# ActuatorBoard.net
KiCad netlist of a schematic drawn in EAGLE
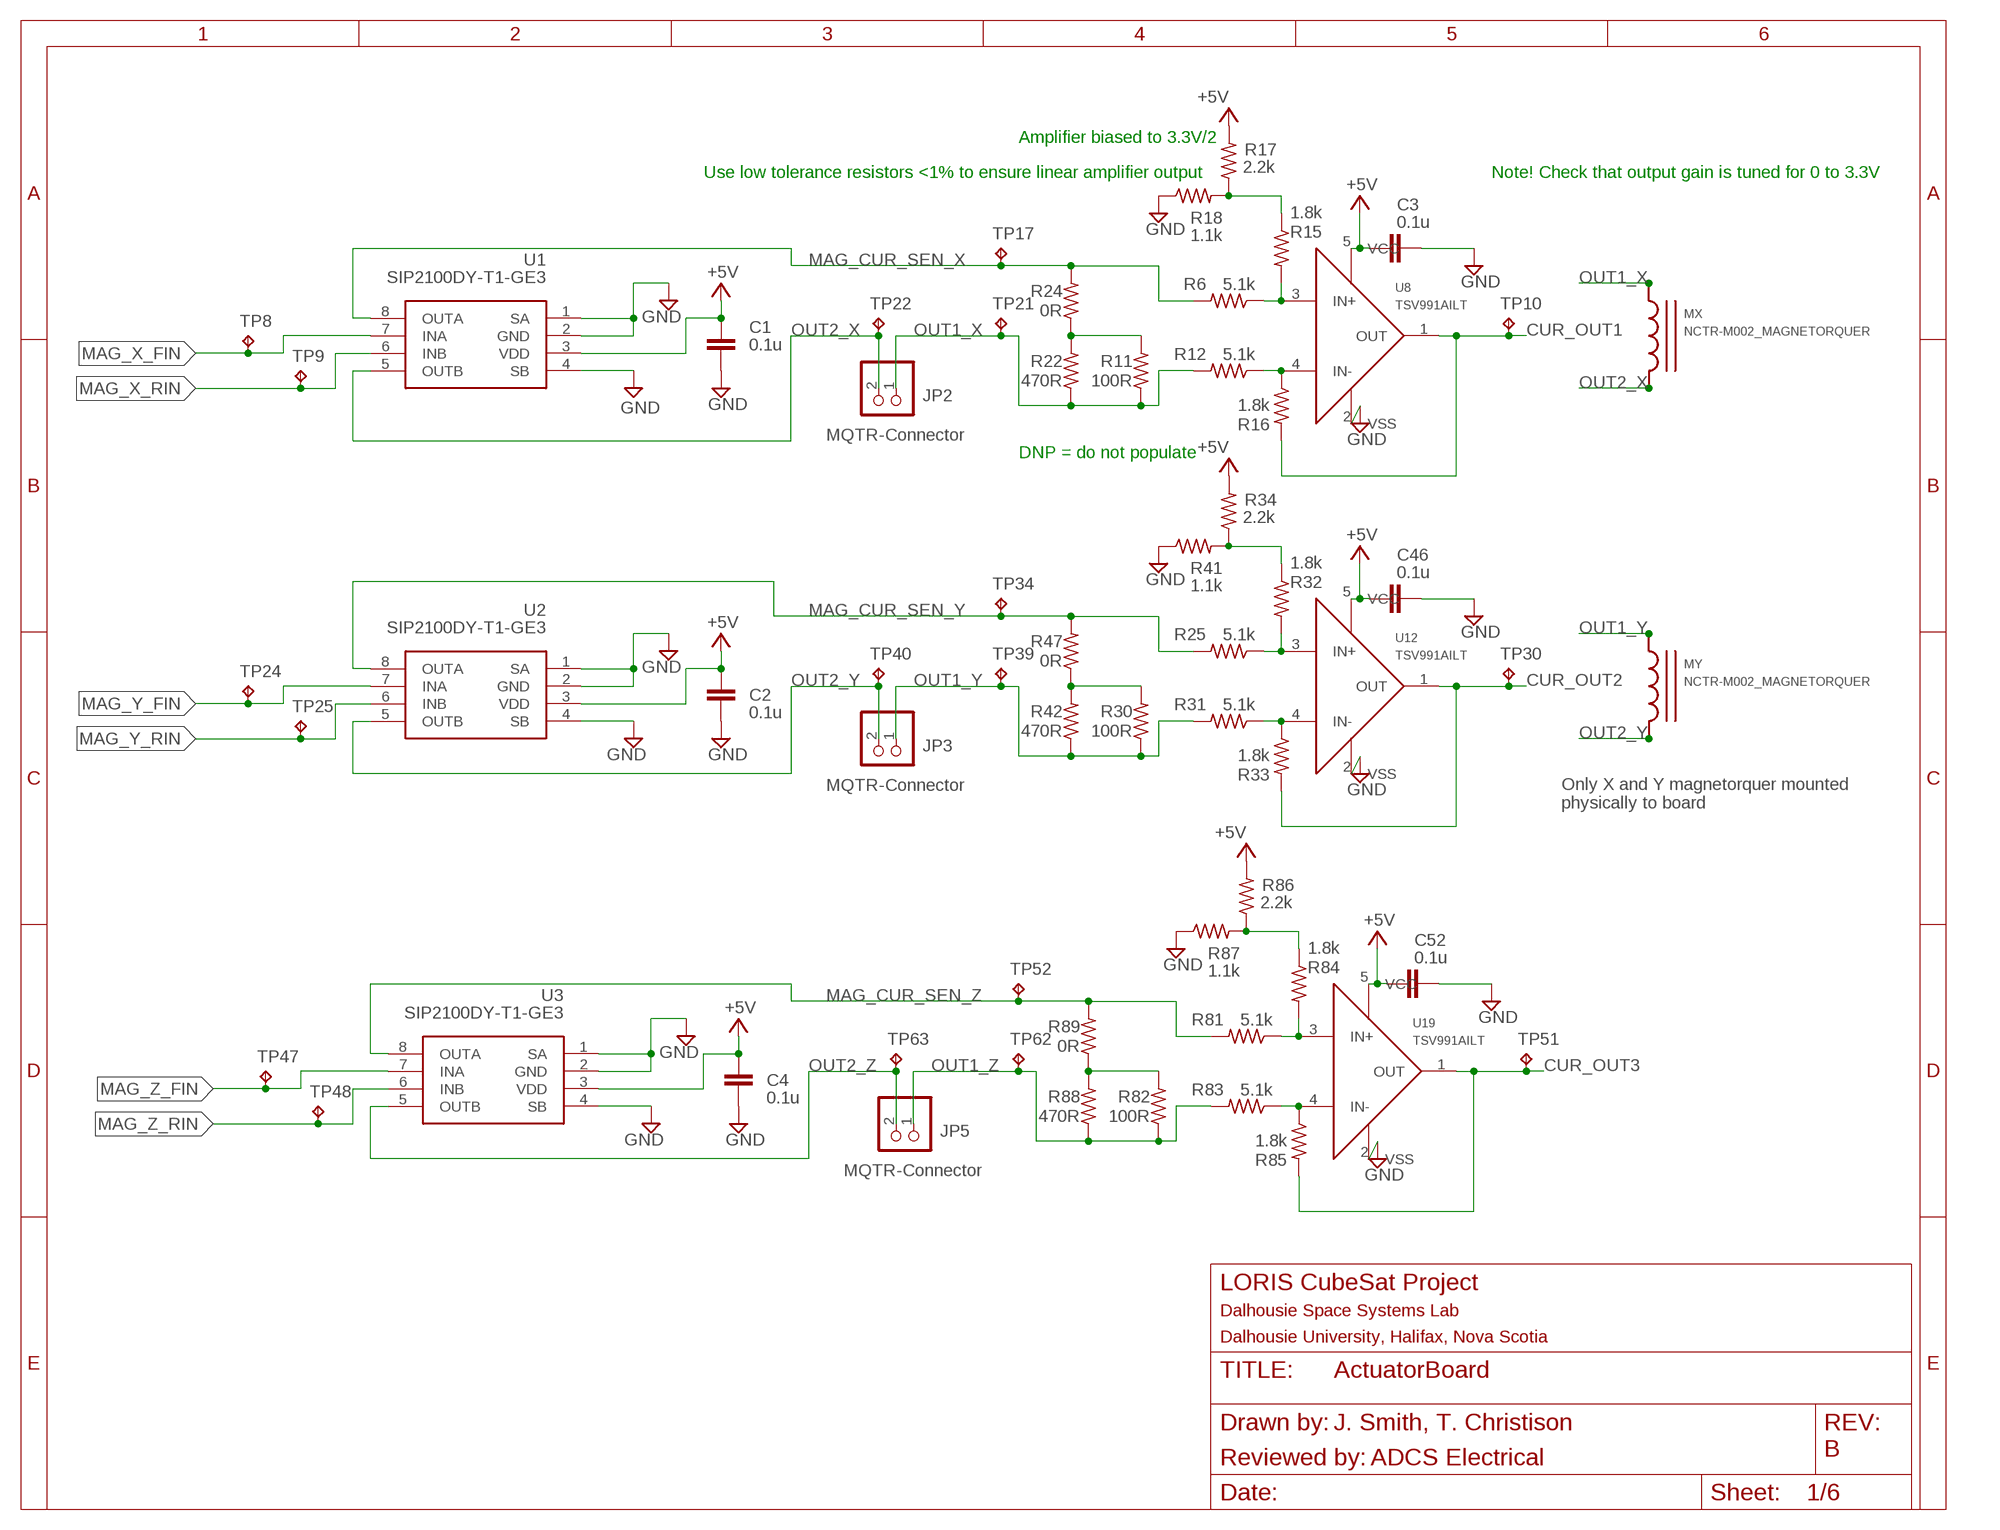
[diagram p0: schematic, sheet 1]
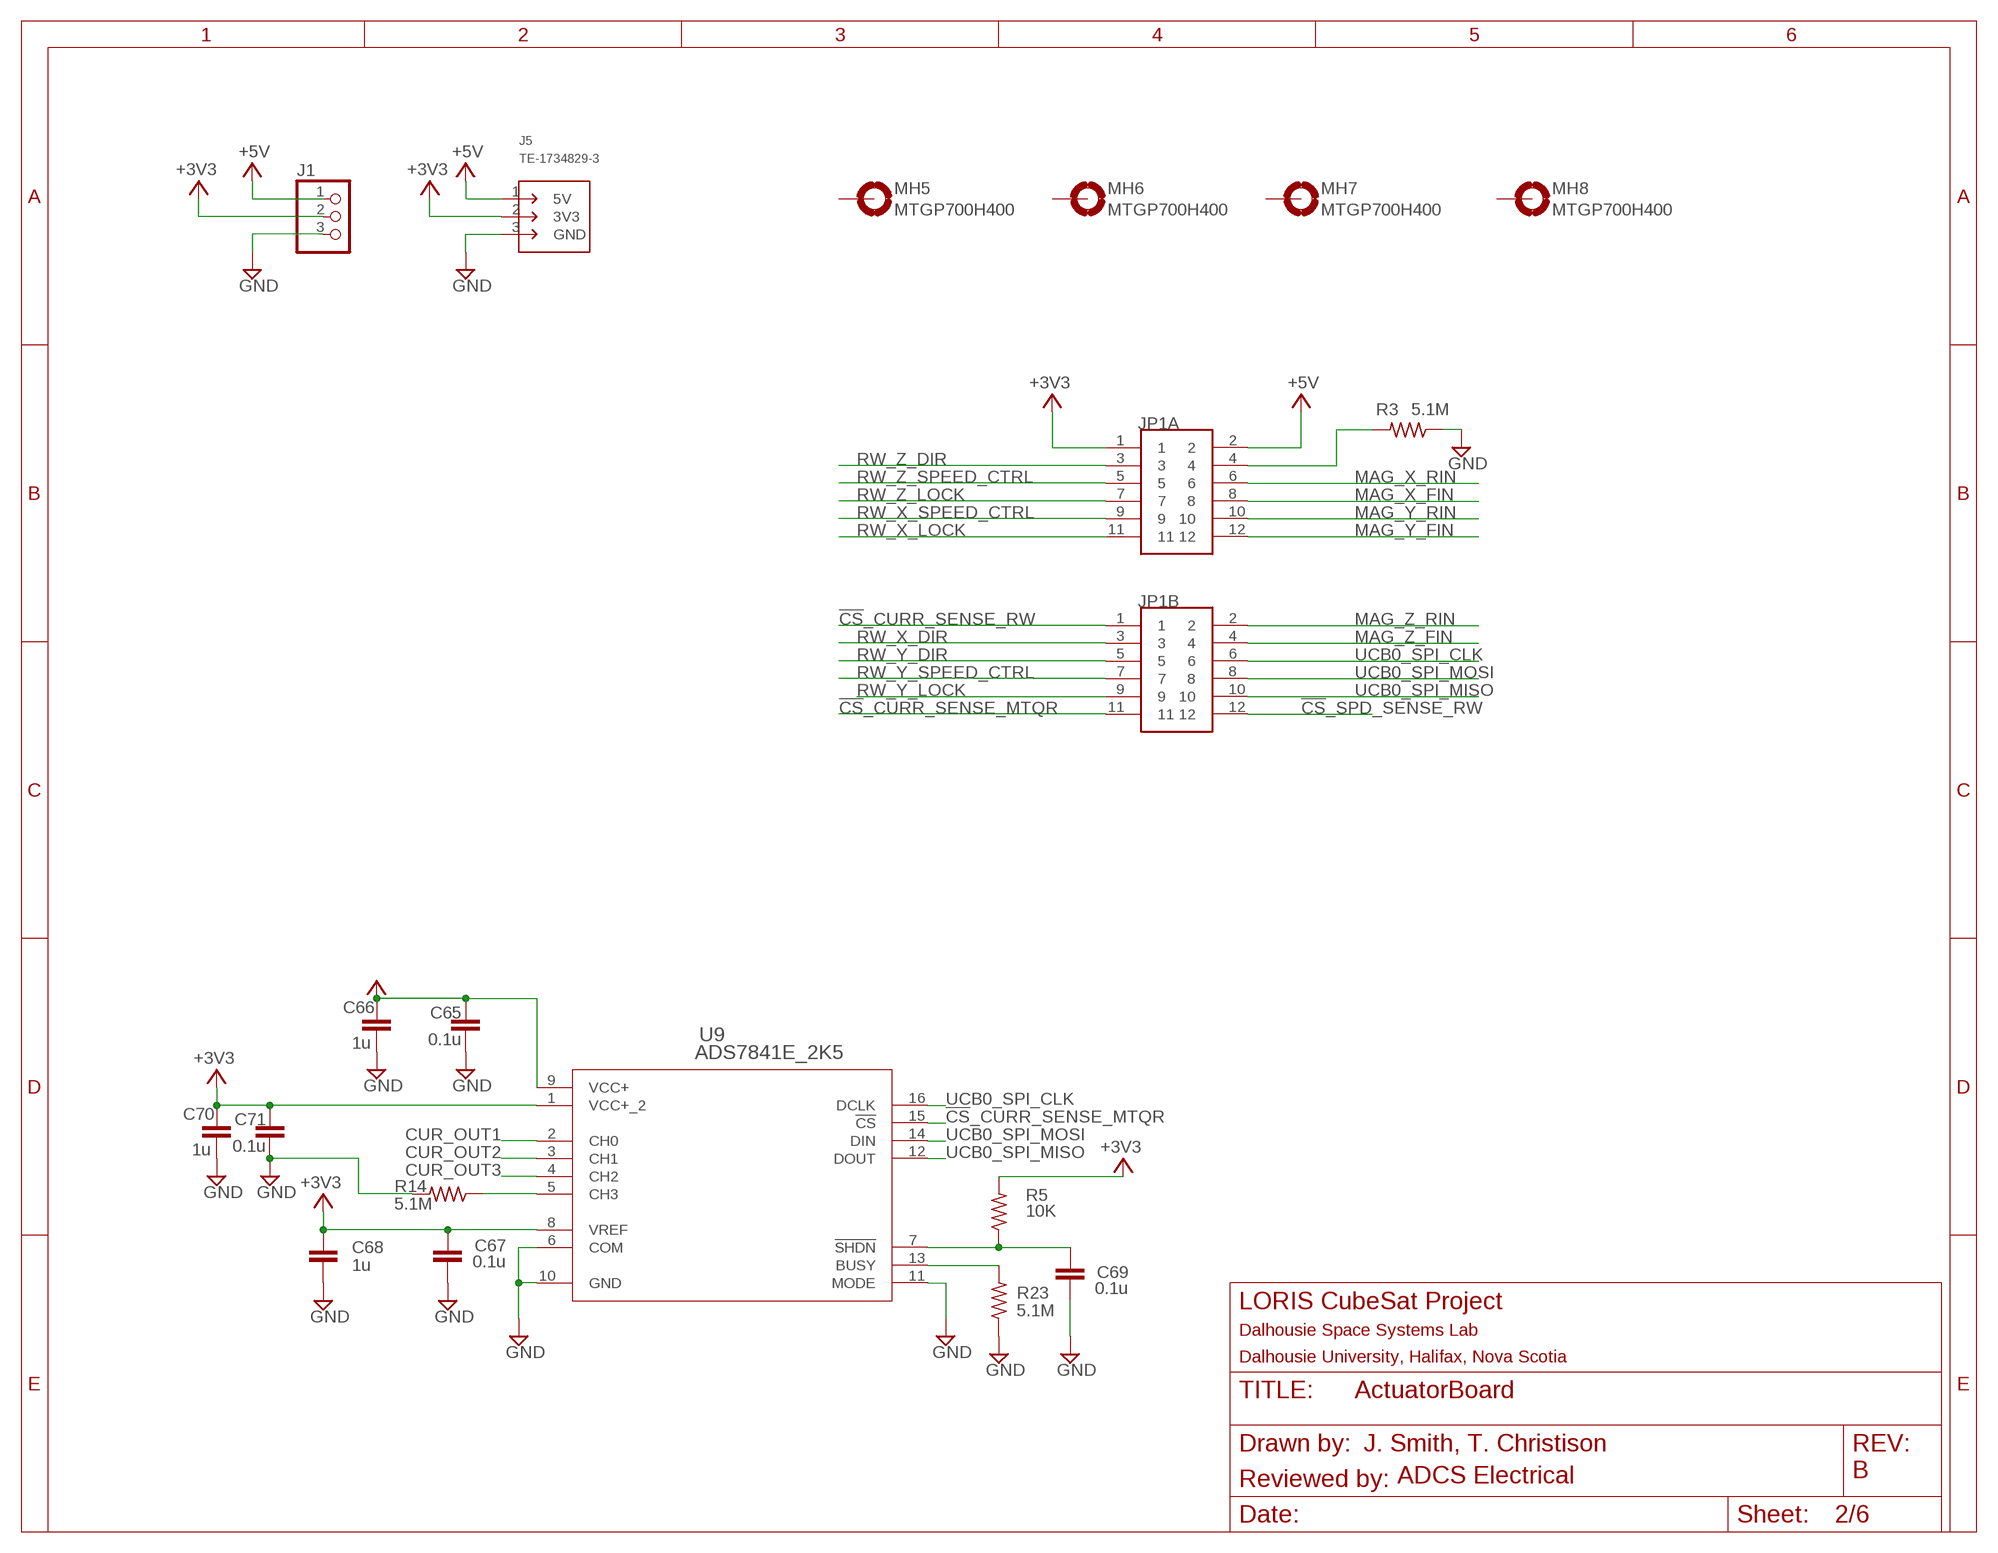
[diagram p1: schematic, sheet 2]
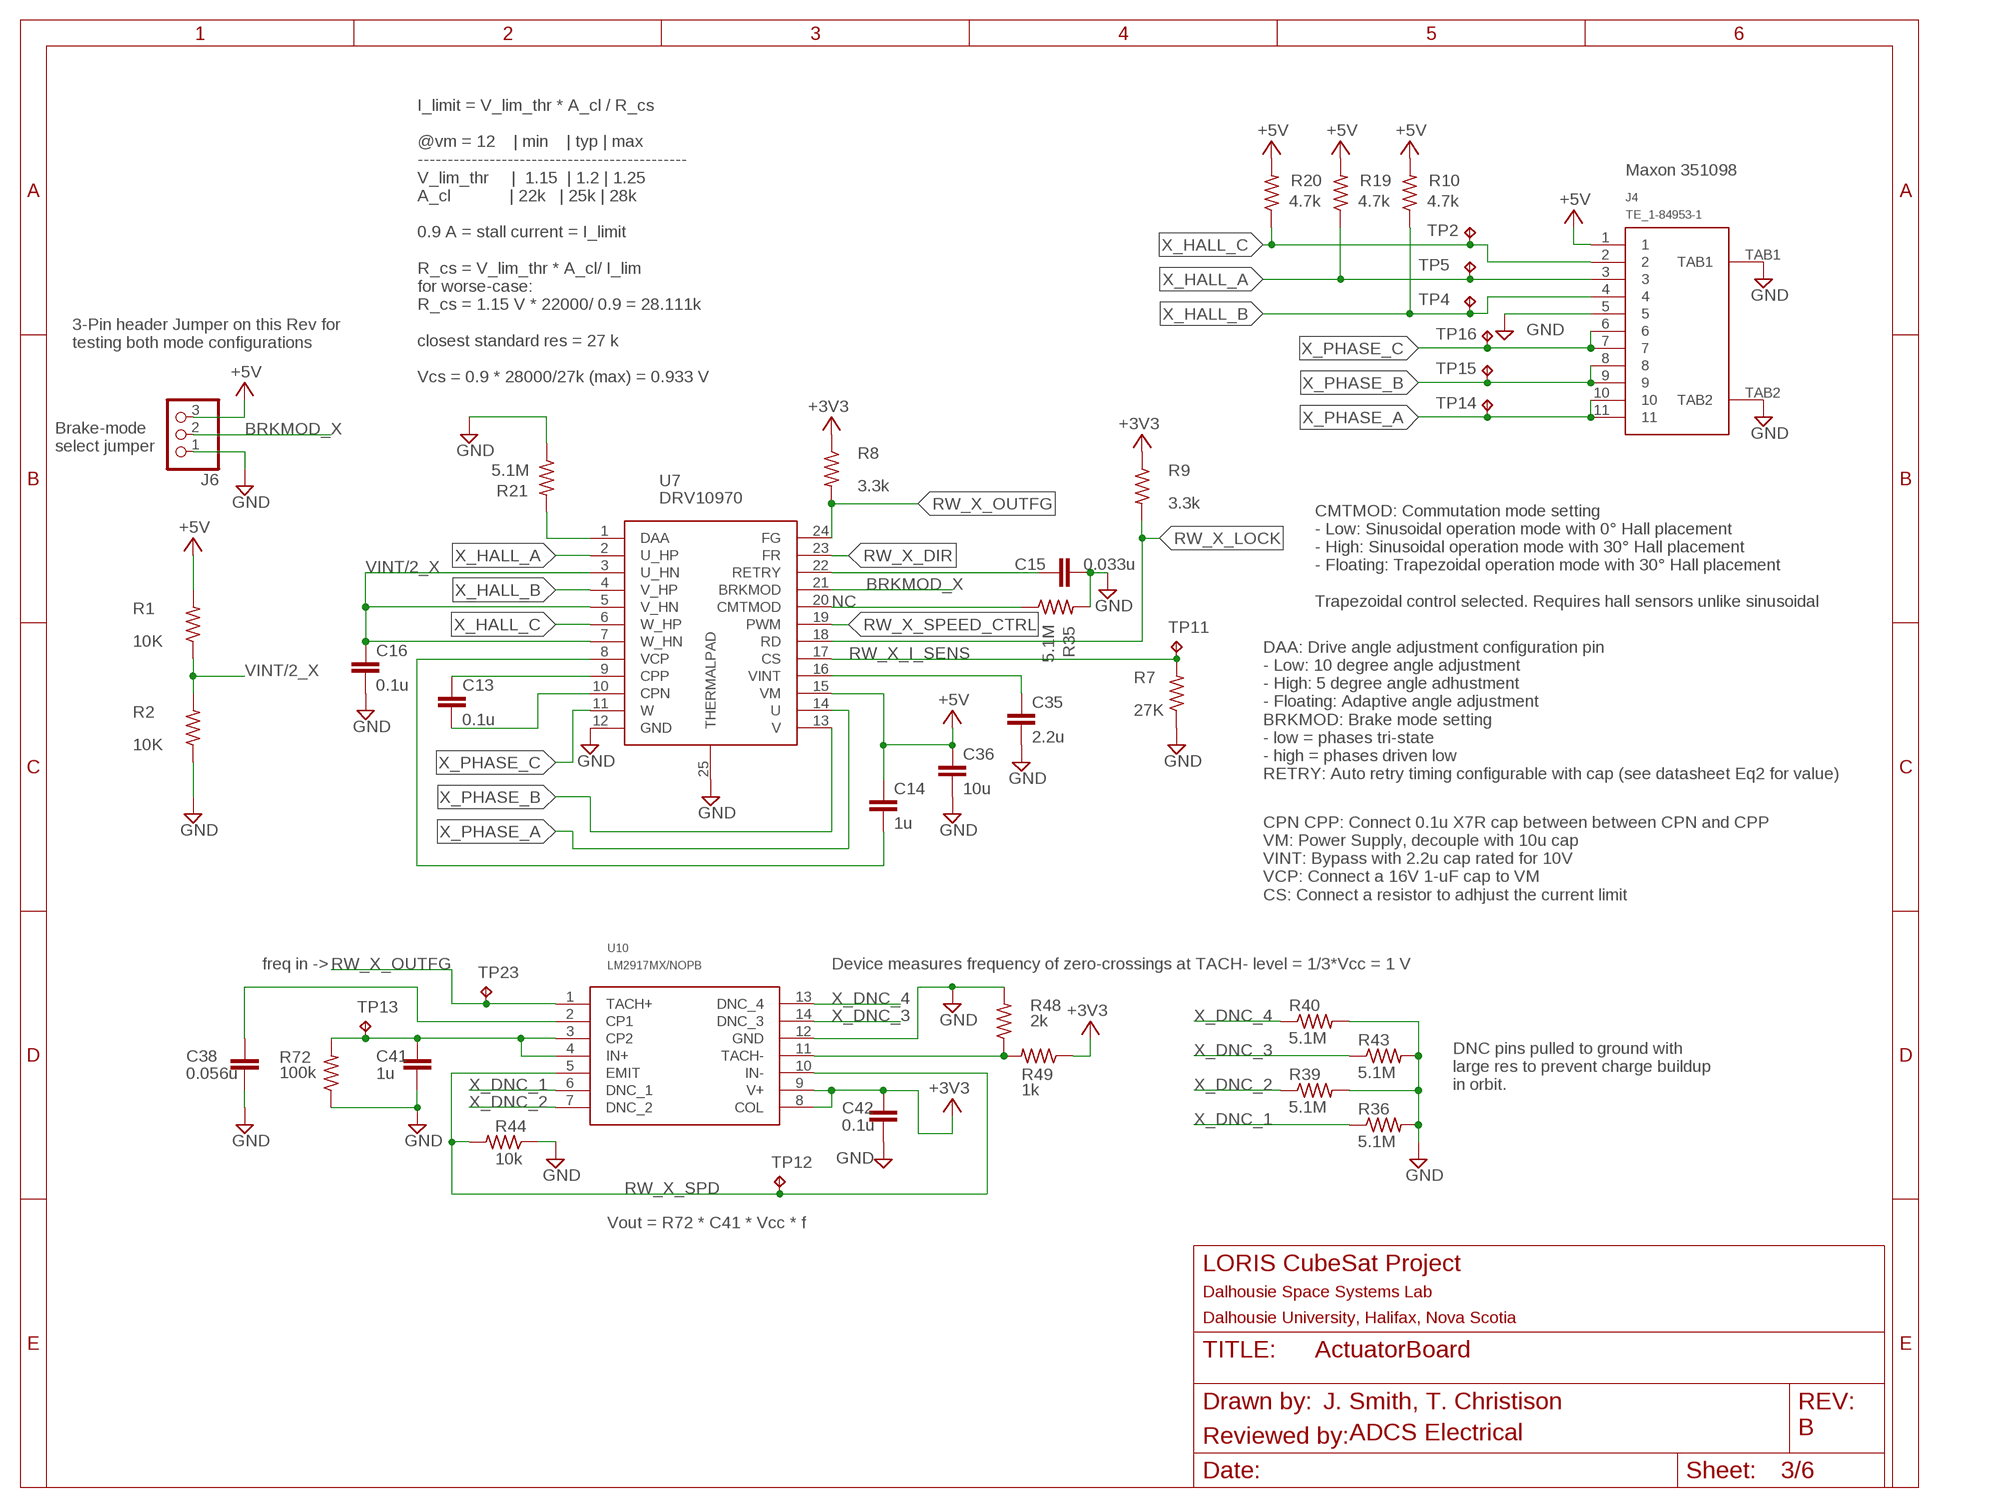
[diagram p2: schematic, sheet 3]
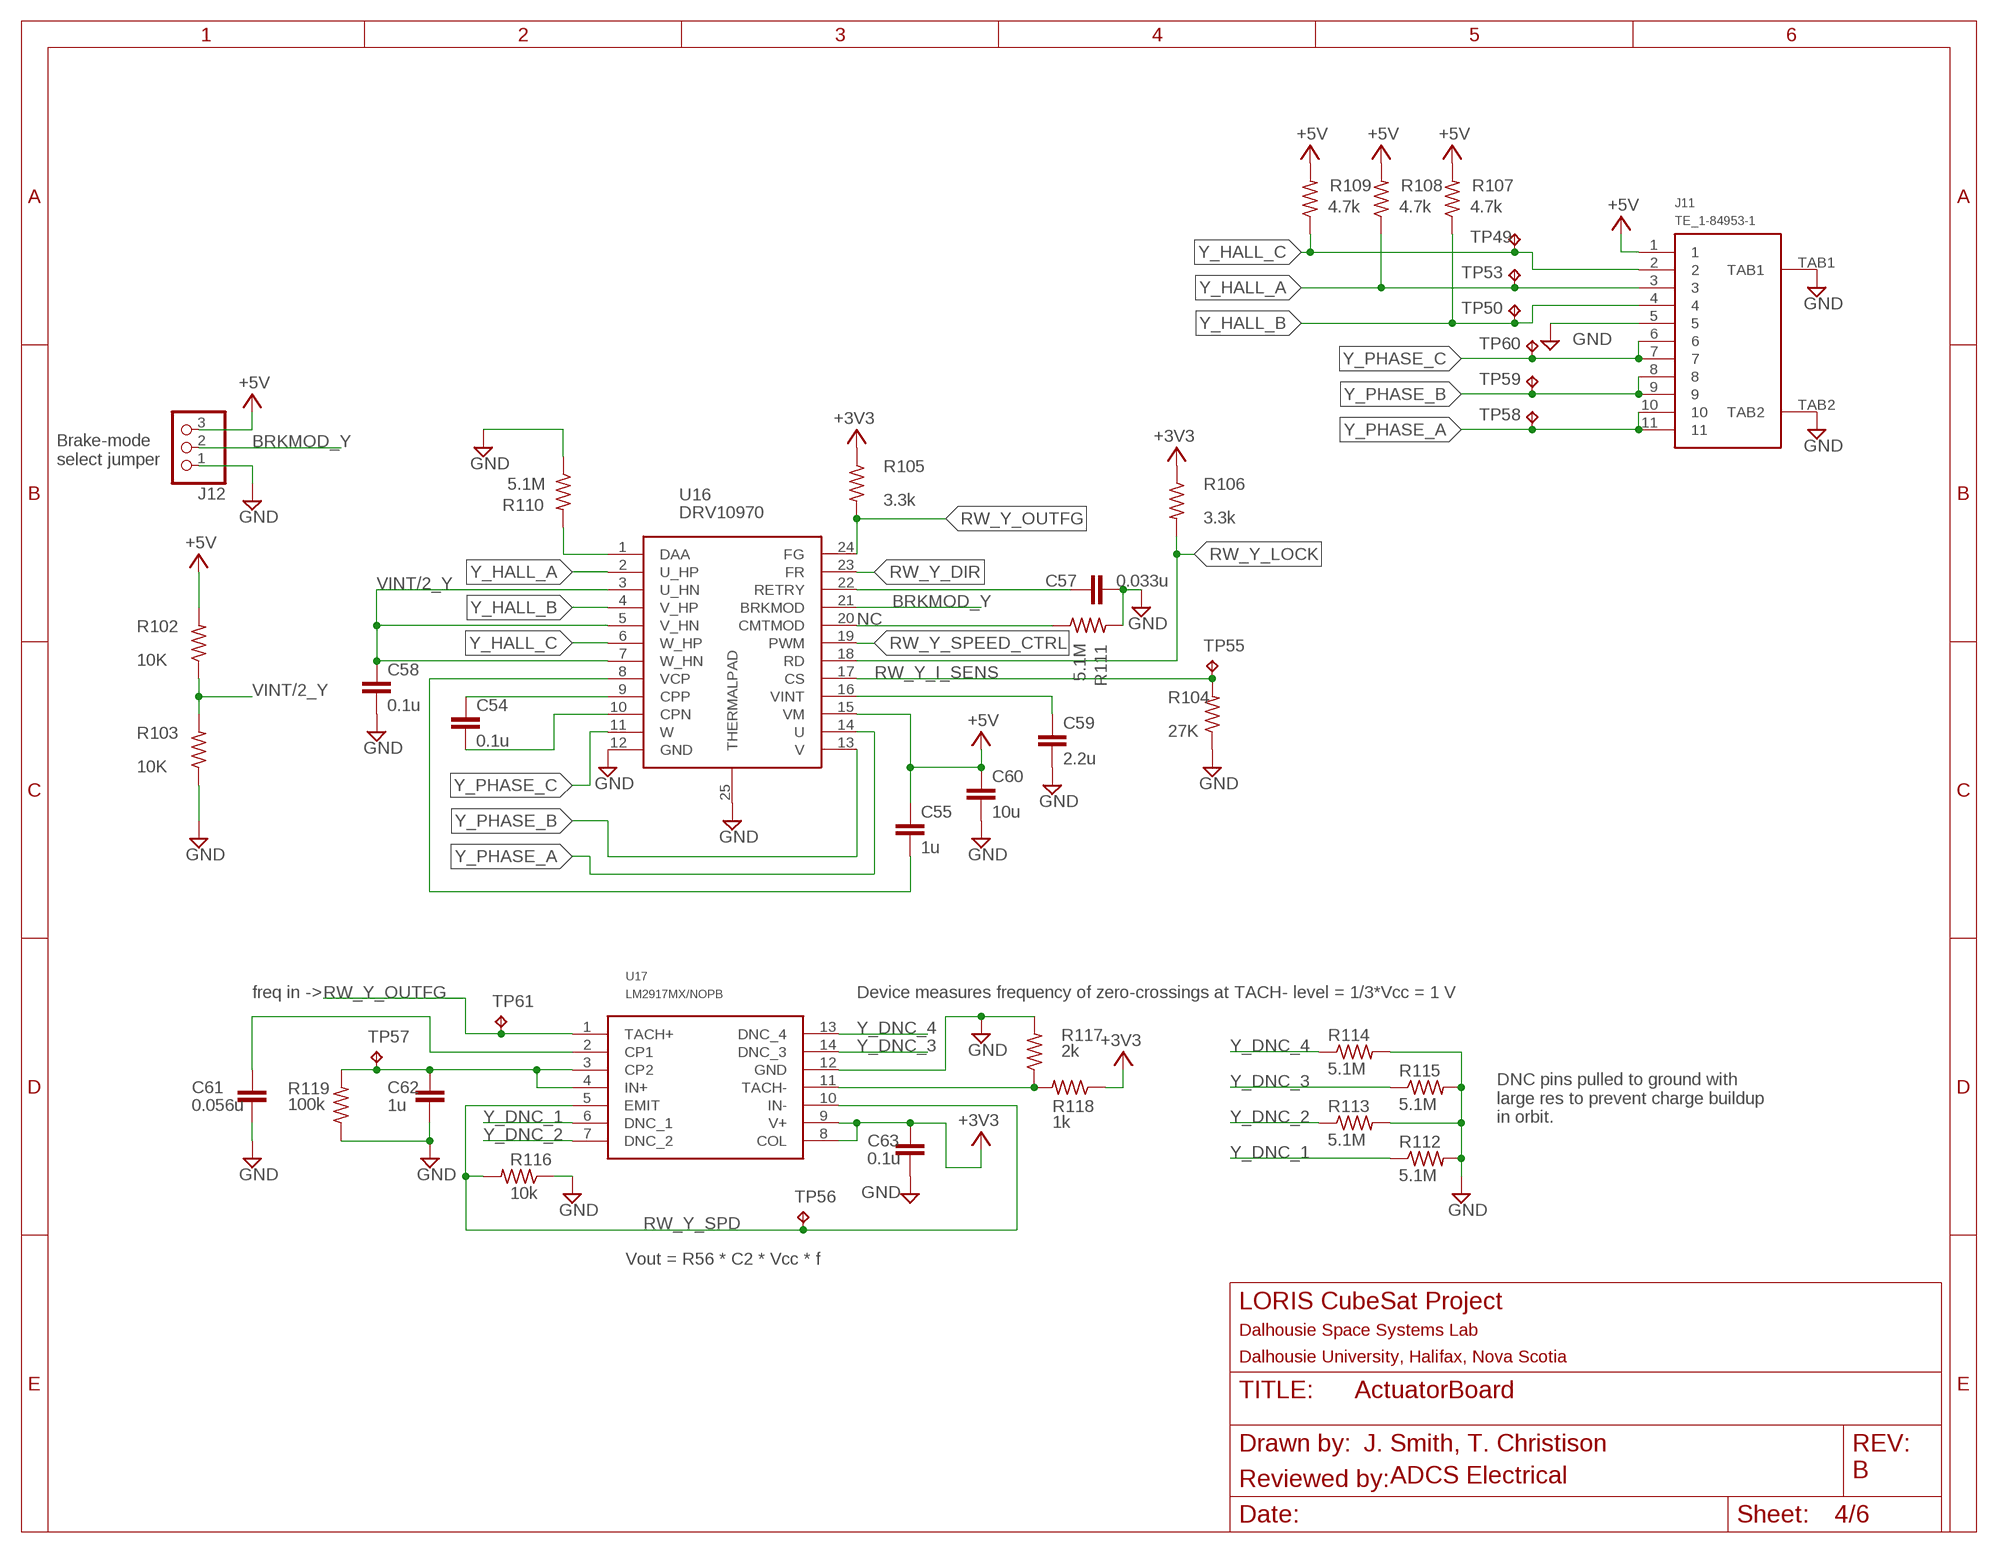
[diagram p3: schematic, sheet 4]
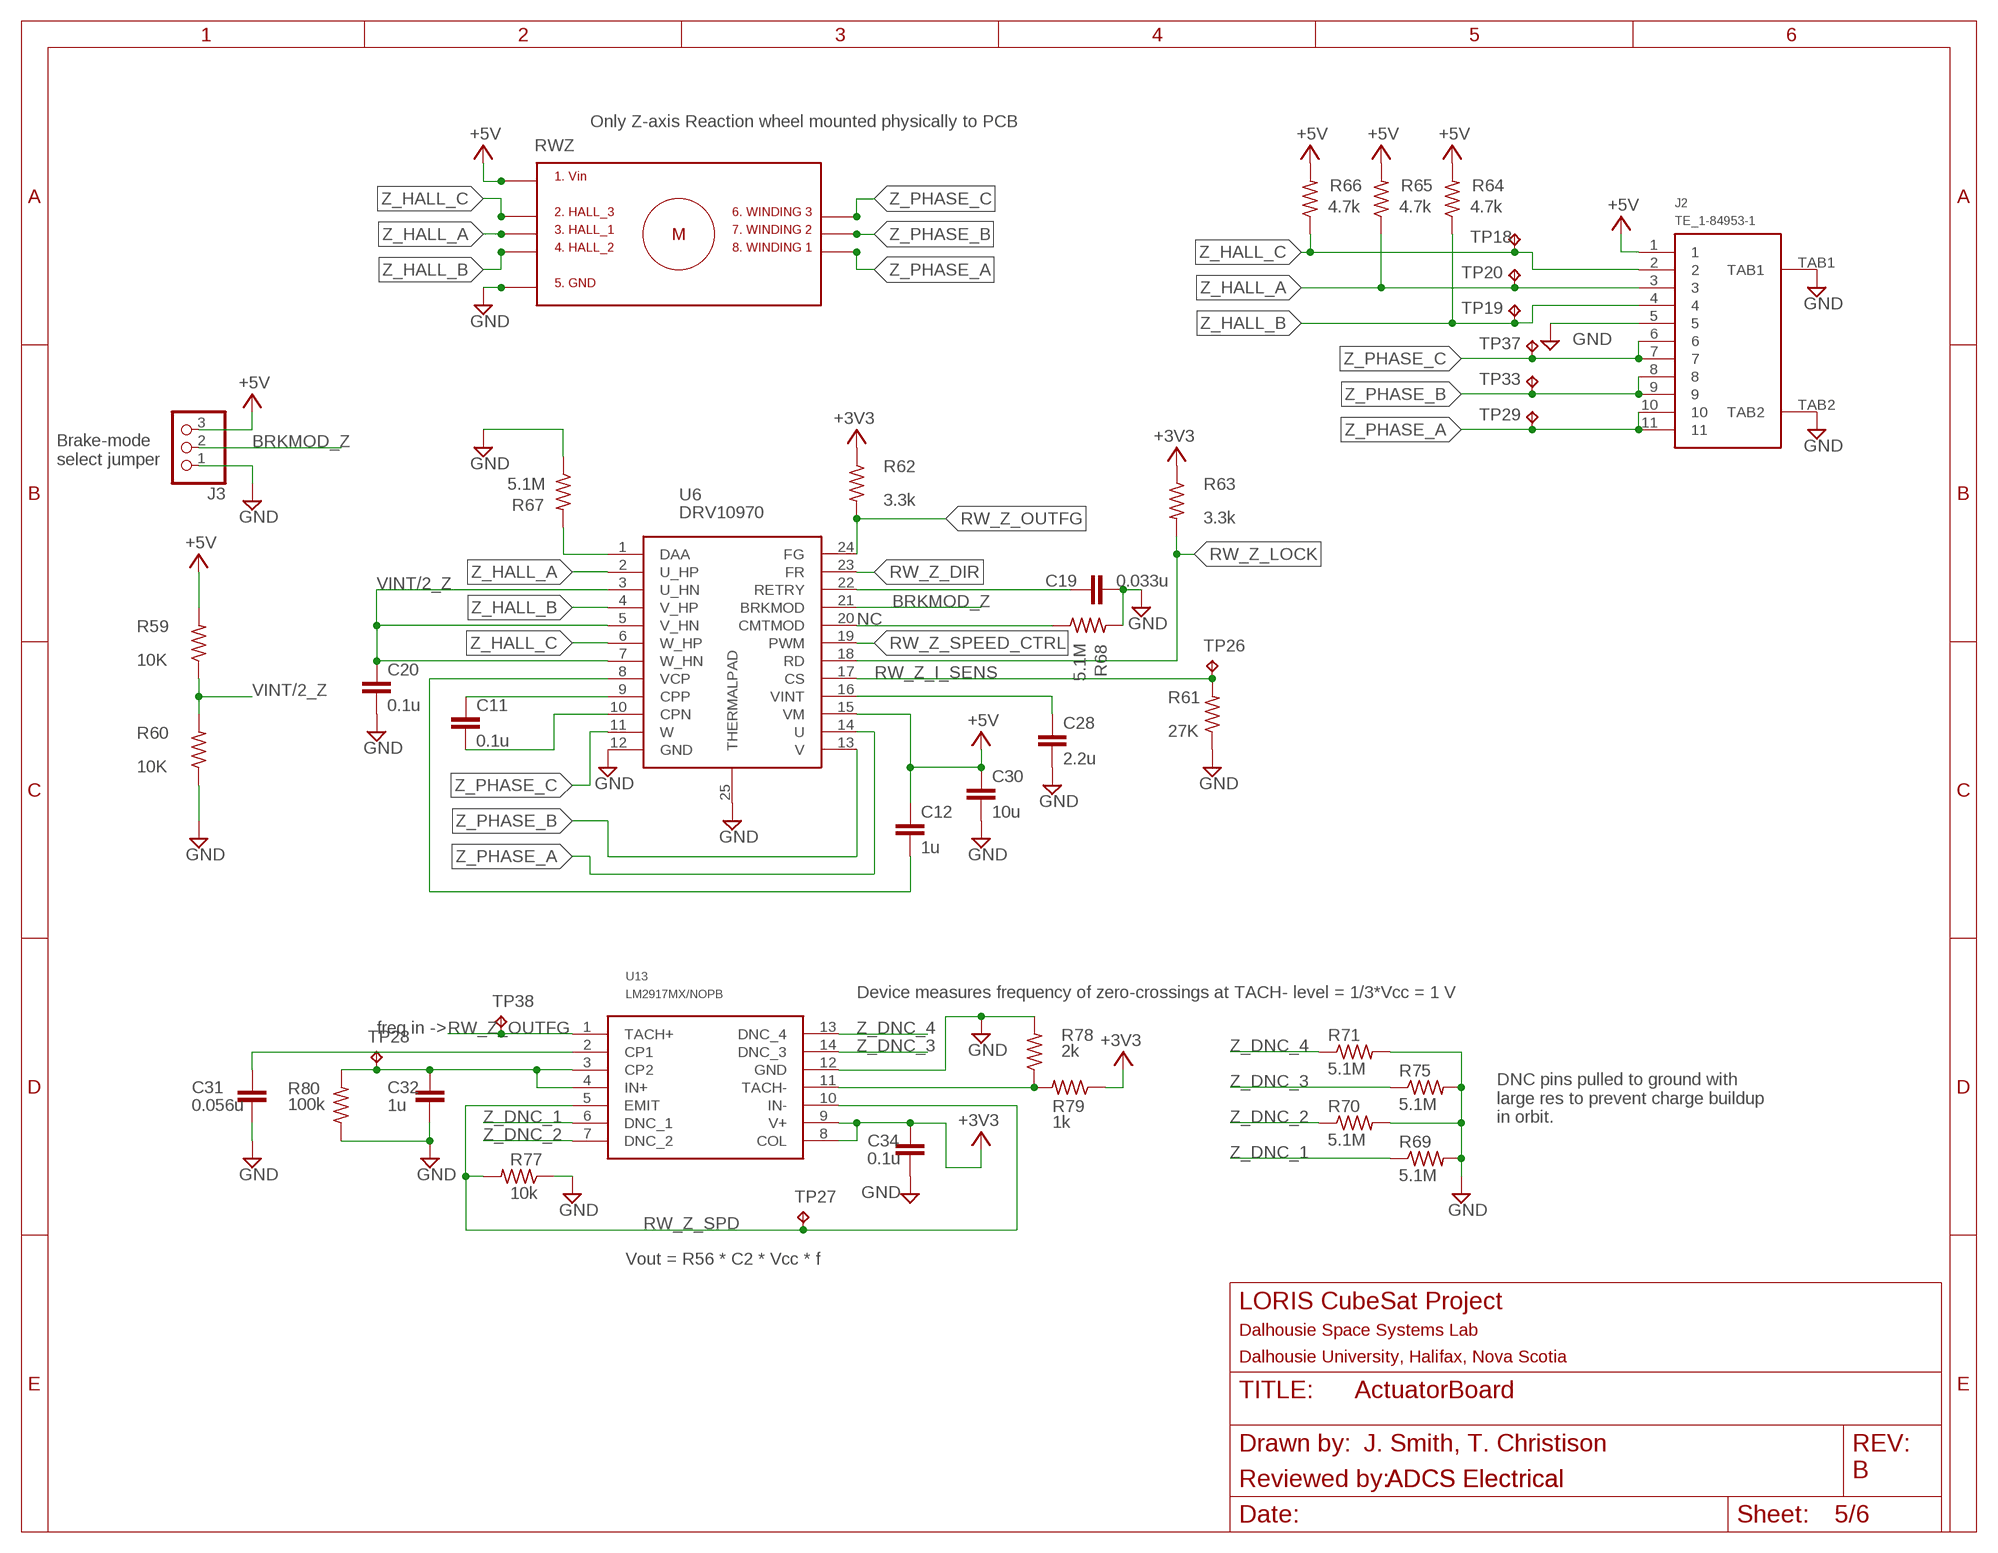
[diagram p4: schematic, sheet 5]
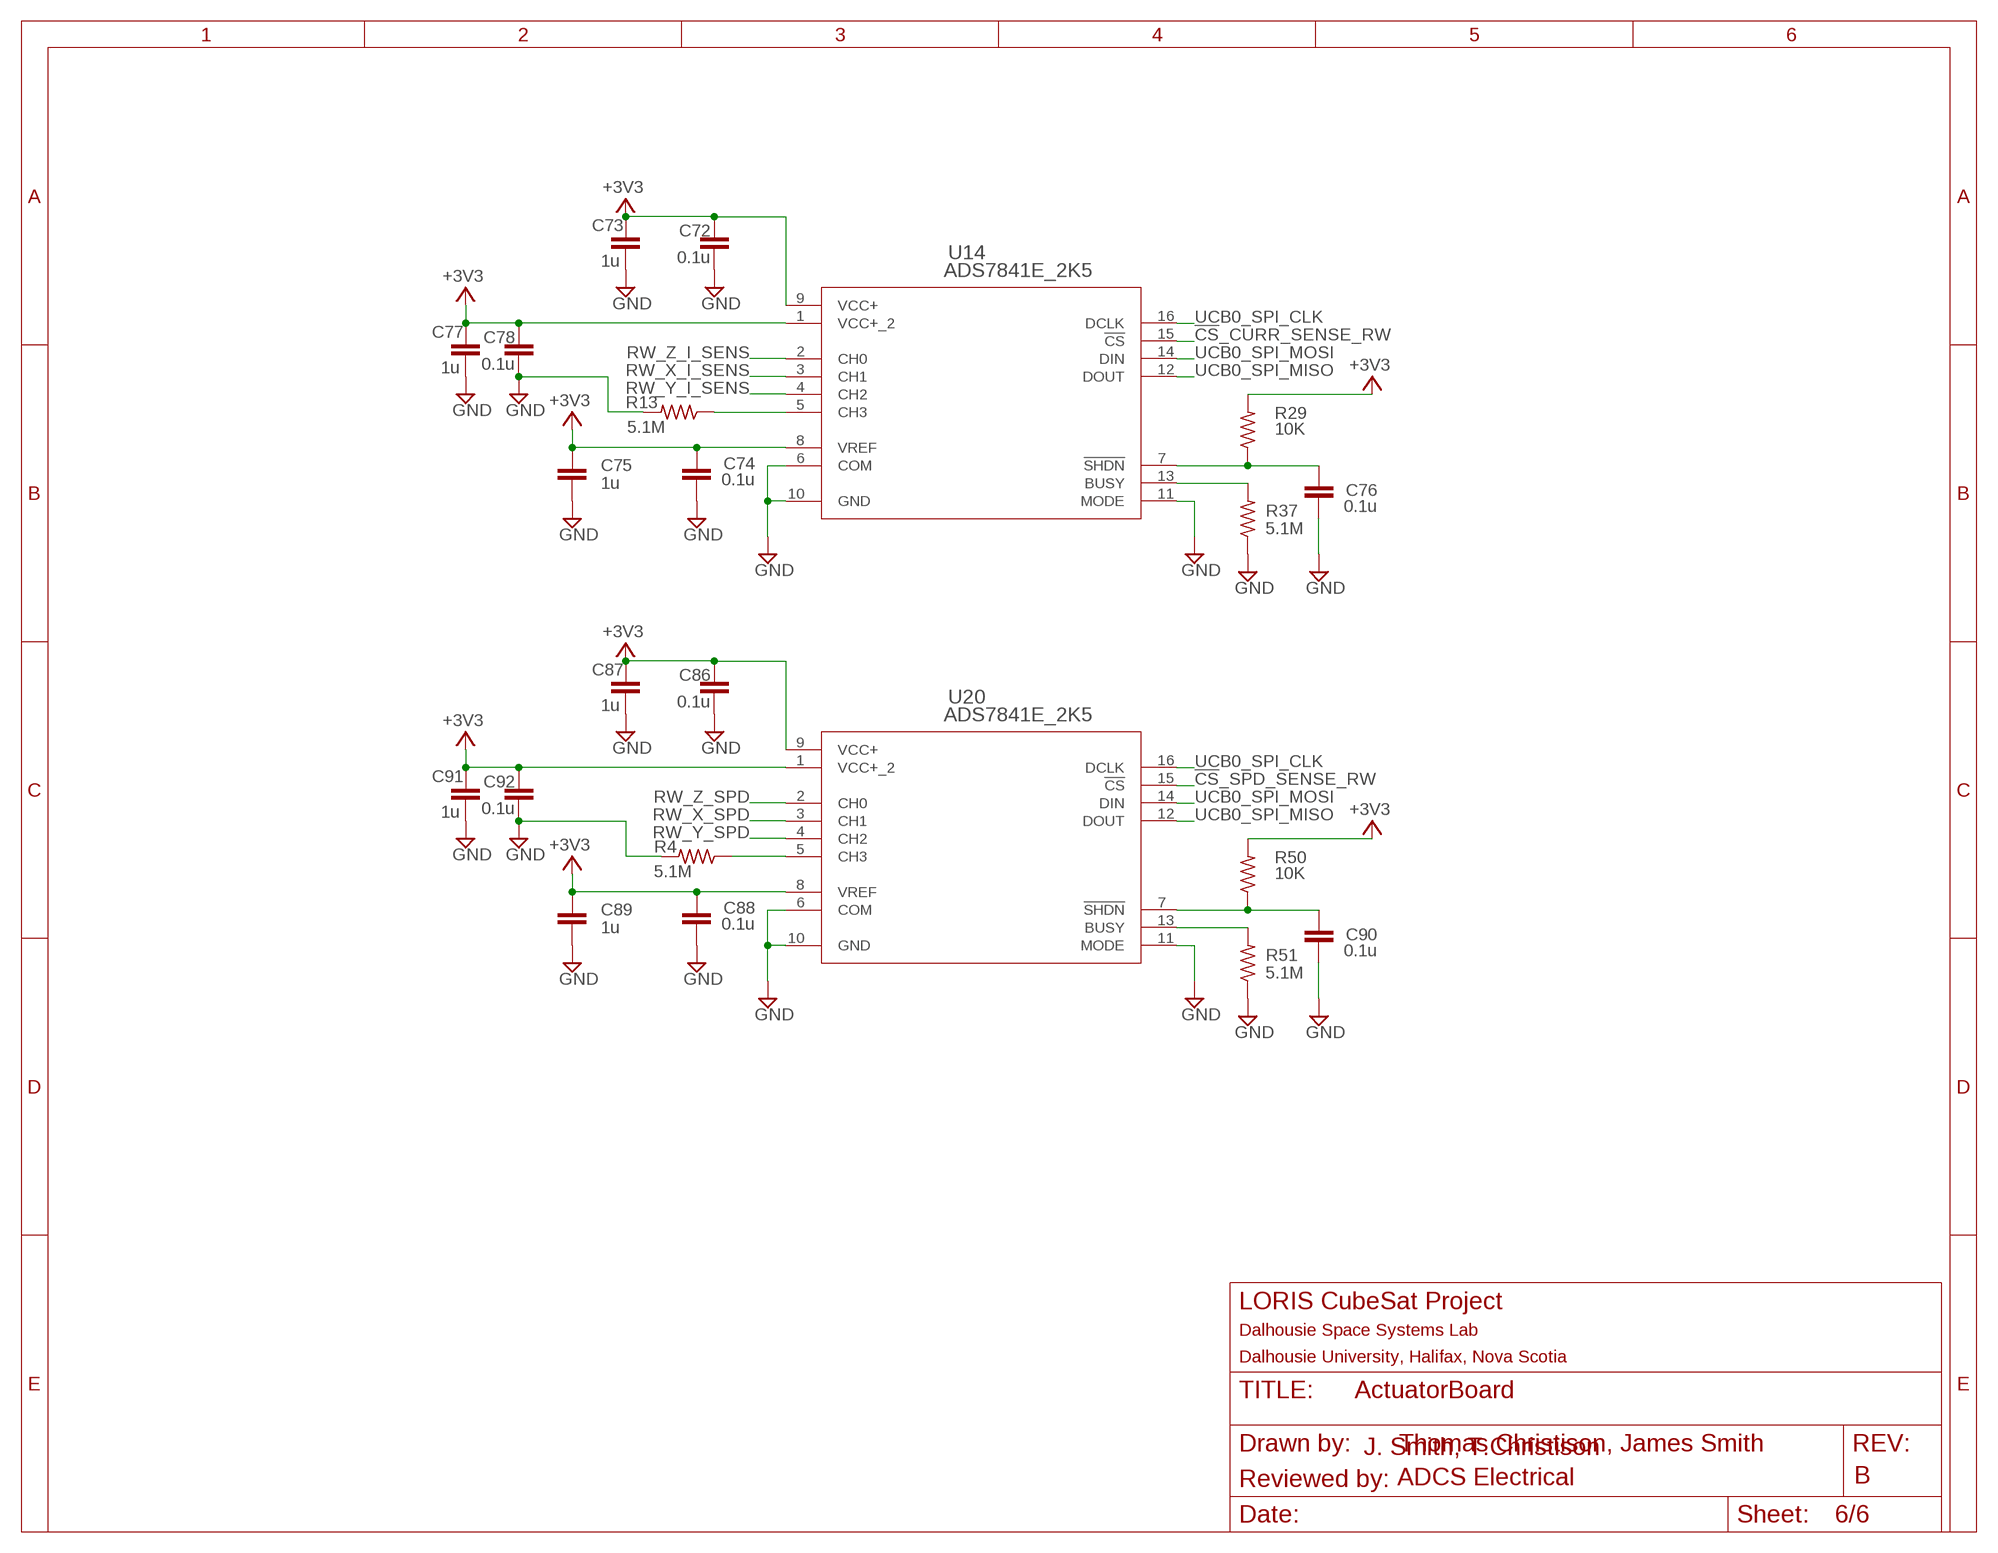
[diagram p5: schematic, sheet 6]

(export (version "E")
  (design (tool "Eeschema 10.0.6"))
  (components
    (comp (ref "C65")
      (value "0.1u")
      (footprint "eagle-import:C0402")
      (libsource (lib "eagle-import") (part "C-EUC0402"))
    )
    (comp (ref "C66")
      (value "1u")
      (footprint "eagle-import:C0402")
      (libsource (lib "eagle-import") (part "C-EUC0402"))
    )
    (comp (ref "C67")
      (value "0.1u")
      (footprint "eagle-import:C0402")
      (libsource (lib "eagle-import") (part "C-EUC0402"))
    )
    (comp (ref "C68")
      (value "1u")
      (footprint "eagle-import:C0402")
      (libsource (lib "eagle-import") (part "C-EUC0402"))
    )
    (comp (ref "C69")
      (value "0.1u")
      (footprint "eagle-import:C0402")
      (libsource (lib "eagle-import") (part "C-EUC0402"))
    )
    (comp (ref "C70")
      (value "1u")
      (footprint "eagle-import:C0402")
      (libsource (lib "eagle-import") (part "C-EUC0402"))
    )
    (comp (ref "C71")
      (value "0.1u")
      (footprint "eagle-import:C0402")
      (libsource (lib "eagle-import") (part "C-EUC0402"))
    )
    (comp (ref "J1")
      (value "PINHD-1X3")
      (footprint "eagle-import:1X03")
      (libsource (lib "eagle-import") (part "PINHD-1X3"))
    )
    (comp (ref "J5")
      (value "TE-1734829-3")
      (footprint "eagle-import:TE-1734829-3")
      (libsource (lib "eagle-import") (part "TE-1734829-3"))
    )
    (comp (ref "JP1A")
      (value "832-10-012-10-005000")
      (footprint "eagle-import:832-10-012-10-005000")
      (fields (field (name "COMMENT") "2355104-4") (field (name "MF") "TE Connectivity"))
      (libsource (lib "eagle-import") (part "832-10-012-10-005000"))
    )
    (comp (ref "JP1B")
      (value "832-10-012-10-005000")
      (footprint "eagle-import:832-10-012-10-005000")
      (fields (field (name "COMMENT") "2355104-4") (field (name "MF") "TE Connectivity"))
      (libsource (lib "eagle-import") (part "832-10-012-10-005000"))
    )
    (comp (ref "MH5")
      (value "MTGP700H400")
      (footprint "eagle-import:MTGP700H400")
      (libsource (lib "eagle-import") (part "MTGP700H400"))
    )
    (comp (ref "MH6")
      (value "MTGP700H400")
      (footprint "eagle-import:MTGP700H400")
      (libsource (lib "eagle-import") (part "MTGP700H400"))
    )
    (comp (ref "MH7")
      (value "MTGP700H400")
      (footprint "eagle-import:MTGP700H400")
      (libsource (lib "eagle-import") (part "MTGP700H400"))
    )
    (comp (ref "MH8")
      (value "MTGP700H400")
      (footprint "eagle-import:MTGP700H400")
      (libsource (lib "eagle-import") (part "MTGP700H400"))
    )
    (comp (ref "R3")
      (value "5.1M")
      (footprint "eagle-import:R0402")
      (libsource (lib "eagle-import") (part "R-US_R0402"))
    )
    (comp (ref "R5")
      (value "10K")
      (footprint "eagle-import:R0402")
      (libsource (lib "eagle-import") (part "R-US_R0402"))
    )
    (comp (ref "R14")
      (value "5.1M")
      (footprint "eagle-import:R0402")
      (libsource (lib "eagle-import") (part "R-US_R0402"))
    )
    (comp (ref "R23")
      (value "5.1M")
      (footprint "eagle-import:R0402")
      (libsource (lib "eagle-import") (part "R-US_R0402"))
    )
    (comp (ref "U9")
      (value "ADS7841E_2K5")
      (footprint "eagle-import:DBQ16")
      (fields
        (field (name "GENERIC_PART_NUMBER") "ADS7841")
        (field (name "MANUFACTURER") "Texas Instruments")
      )
      (libsource (lib "eagle-import") (part "ADS7841E_2K5"))
    )
    (comp (ref "C1")
      (value "0.1u")
      (footprint "eagle-import:C0603")
      (libsource (lib "eagle-import") (part "C-EUC0603"))
    )
    (comp (ref "C2")
      (value "0.1u")
      (footprint "eagle-import:C0603")
      (libsource (lib "eagle-import") (part "C-EUC0603"))
    )
    (comp (ref "C3")
      (value "0.1u")
      (footprint "eagle-import:C0402")
      (libsource (lib "eagle-import") (part "C-EUC0402"))
    )
    (comp (ref "C4")
      (value "0.1u")
      (footprint "eagle-import:C0603")
      (libsource (lib "eagle-import") (part "C-EUC0603"))
    )
    (comp (ref "C46")
      (value "0.1u")
      (footprint "eagle-import:C0402")
      (libsource (lib "eagle-import") (part "C-EUC0402"))
    )
    (comp (ref "C52")
      (value "0.1u")
      (footprint "eagle-import:C0402")
      (libsource (lib "eagle-import") (part "C-EUC0402"))
    )
    (comp (ref "JP2")
      (value "PINHD-1X2")
      (footprint "eagle-import:1X02")
      (libsource (lib "eagle-import") (part "PINHD-1X2"))
    )
    (comp (ref "JP3")
      (value "PINHD-1X2")
      (footprint "eagle-import:1X02")
      (libsource (lib "eagle-import") (part "PINHD-1X2"))
    )
    (comp (ref "JP5")
      (value "PINHD-1X2")
      (footprint "eagle-import:1X02")
      (libsource (lib "eagle-import") (part "PINHD-1X2"))
    )
    (comp (ref "MX")
      (value "NCTR-M002_MAGNETORQUER")
      (footprint "eagle-import:MAG_MOUNT_V3")
      (libsource (lib "eagle-import") (part "NCTR-M002_MAGNETORQUER"))
    )
    (comp (ref "MY")
      (value "NCTR-M002_MAGNETORQUER")
      (footprint "eagle-import:MAG_MOUNT_V3")
      (libsource (lib "eagle-import") (part "NCTR-M002_MAGNETORQUER"))
    )
    (comp (ref "R6")
      (value "5.1k")
      (footprint "eagle-import:R0402")
      (libsource (lib "eagle-import") (part "R-US_R0402"))
    )
    (comp (ref "R11")
      (value "100R")
      (footprint "eagle-import:R0805")
      (libsource (lib "eagle-import") (part "R-US_R0805"))
    )
    (comp (ref "R12")
      (value "5.1k")
      (footprint "eagle-import:R0402")
      (libsource (lib "eagle-import") (part "R-US_R0402"))
    )
    (comp (ref "R15")
      (value "1.8k")
      (footprint "eagle-import:R0402")
      (libsource (lib "eagle-import") (part "R-US_R0402"))
    )
    (comp (ref "R16")
      (value "1.8k")
      (footprint "eagle-import:R0402")
      (libsource (lib "eagle-import") (part "R-US_R0402"))
    )
    (comp (ref "R17")
      (value "2.2k")
      (footprint "eagle-import:R0402")
      (libsource (lib "eagle-import") (part "R-US_R0402"))
    )
    (comp (ref "R18")
      (value "1.1k")
      (footprint "eagle-import:R0402")
      (libsource (lib "eagle-import") (part "R-US_R0402"))
    )
    (comp (ref "R22")
      (value "470R")
      (footprint "eagle-import:R0805")
      (libsource (lib "eagle-import") (part "R-US_R0805"))
    )
    (comp (ref "R24")
      (value "0R")
      (footprint "eagle-import:R0805")
      (libsource (lib "eagle-import") (part "R-US_R0805"))
    )
    (comp (ref "R25")
      (value "5.1k")
      (footprint "eagle-import:R0402")
      (libsource (lib "eagle-import") (part "R-US_R0402"))
    )
    (comp (ref "R30")
      (value "100R")
      (footprint "eagle-import:R0805")
      (libsource (lib "eagle-import") (part "R-US_R0805"))
    )
    (comp (ref "R31")
      (value "5.1k")
      (footprint "eagle-import:R0402")
      (libsource (lib "eagle-import") (part "R-US_R0402"))
    )
    (comp (ref "R32")
      (value "1.8k")
      (footprint "eagle-import:R0402")
      (libsource (lib "eagle-import") (part "R-US_R0402"))
    )
    (comp (ref "R33")
      (value "1.8k")
      (footprint "eagle-import:R0402")
      (libsource (lib "eagle-import") (part "R-US_R0402"))
    )
    (comp (ref "R34")
      (value "2.2k")
      (footprint "eagle-import:R0402")
      (libsource (lib "eagle-import") (part "R-US_R0402"))
    )
    (comp (ref "R41")
      (value "1.1k")
      (footprint "eagle-import:R0402")
      (libsource (lib "eagle-import") (part "R-US_R0402"))
    )
    (comp (ref "R42")
      (value "470R")
      (footprint "eagle-import:R0805")
      (libsource (lib "eagle-import") (part "R-US_R0805"))
    )
    (comp (ref "R47")
      (value "0R")
      (footprint "eagle-import:R0805")
      (libsource (lib "eagle-import") (part "R-US_R0805"))
    )
    (comp (ref "R81")
      (value "5.1k")
      (footprint "eagle-import:R0402")
      (libsource (lib "eagle-import") (part "R-US_R0402"))
    )
    (comp (ref "R82")
      (value "100R")
      (footprint "eagle-import:R0805")
      (libsource (lib "eagle-import") (part "R-US_R0805"))
    )
    (comp (ref "R83")
      (value "5.1k")
      (footprint "eagle-import:R0402")
      (libsource (lib "eagle-import") (part "R-US_R0402"))
    )
    (comp (ref "R84")
      (value "1.8k")
      (footprint "eagle-import:R0402")
      (libsource (lib "eagle-import") (part "R-US_R0402"))
    )
    (comp (ref "R85")
      (value "1.8k")
      (footprint "eagle-import:R0402")
      (libsource (lib "eagle-import") (part "R-US_R0402"))
    )
    (comp (ref "R86")
      (value "2.2k")
      (footprint "eagle-import:R0402")
      (libsource (lib "eagle-import") (part "R-US_R0402"))
    )
    (comp (ref "R87")
      (value "1.1k")
      (footprint "eagle-import:R0402")
      (libsource (lib "eagle-import") (part "R-US_R0402"))
    )
    (comp (ref "R88")
      (value "470R")
      (footprint "eagle-import:R0805")
      (libsource (lib "eagle-import") (part "R-US_R0805"))
    )
    (comp (ref "R89")
      (value "0R")
      (footprint "eagle-import:R0805")
      (libsource (lib "eagle-import") (part "R-US_R0805"))
    )
    (comp (ref "TP8")
      (value "TESTPOINT")
      (footprint "eagle-import:TP_P76H50")
      (libsource (lib "eagle-import") (part "TESTPOINT"))
    )
    (comp (ref "TP9")
      (value "TESTPOINT")
      (footprint "eagle-import:TP_P76H50")
      (libsource (lib "eagle-import") (part "TESTPOINT"))
    )
    (comp (ref "TP10")
      (value "TESTPOINT")
      (footprint "eagle-import:TP_P76H50")
      (libsource (lib "eagle-import") (part "TESTPOINT"))
    )
    (comp (ref "TP17")
      (value "TESTPOINT")
      (footprint "eagle-import:TP_P76H50")
      (libsource (lib "eagle-import") (part "TESTPOINT"))
    )
    (comp (ref "TP21")
      (value "TESTPOINT")
      (footprint "eagle-import:TP_P76H50")
      (libsource (lib "eagle-import") (part "TESTPOINT"))
    )
    (comp (ref "TP22")
      (value "TESTPOINT")
      (footprint "eagle-import:TP_P76H50")
      (libsource (lib "eagle-import") (part "TESTPOINT"))
    )
    (comp (ref "TP24")
      (value "TESTPOINT")
      (footprint "eagle-import:TP_P76H50")
      (libsource (lib "eagle-import") (part "TESTPOINT"))
    )
    (comp (ref "TP25")
      (value "TESTPOINT")
      (footprint "eagle-import:TP_P76H50")
      (libsource (lib "eagle-import") (part "TESTPOINT"))
    )
    (comp (ref "TP30")
      (value "TESTPOINT")
      (footprint "eagle-import:TP_P76H50")
      (libsource (lib "eagle-import") (part "TESTPOINT"))
    )
    (comp (ref "TP34")
      (value "TESTPOINT")
      (footprint "eagle-import:TP_P76H50")
      (libsource (lib "eagle-import") (part "TESTPOINT"))
    )
    (comp (ref "TP39")
      (value "TESTPOINT")
      (footprint "eagle-import:TP_P76H50")
      (libsource (lib "eagle-import") (part "TESTPOINT"))
    )
    (comp (ref "TP40")
      (value "TESTPOINT")
      (footprint "eagle-import:TP_P76H50")
      (libsource (lib "eagle-import") (part "TESTPOINT"))
    )
    (comp (ref "TP47")
      (value "TESTPOINT")
      (footprint "eagle-import:TP_P76H50")
      (libsource (lib "eagle-import") (part "TESTPOINT"))
    )
    (comp (ref "TP48")
      (value "TESTPOINT")
      (footprint "eagle-import:TP_P76H50")
      (libsource (lib "eagle-import") (part "TESTPOINT"))
    )
    (comp (ref "TP51")
      (value "TESTPOINT")
      (footprint "eagle-import:TP_P76H50")
      (libsource (lib "eagle-import") (part "TESTPOINT"))
    )
    (comp (ref "TP52")
      (value "TESTPOINT")
      (footprint "eagle-import:TP_P76H50")
      (libsource (lib "eagle-import") (part "TESTPOINT"))
    )
    (comp (ref "TP62")
      (value "TESTPOINT")
      (footprint "eagle-import:TP_P76H50")
      (libsource (lib "eagle-import") (part "TESTPOINT"))
    )
    (comp (ref "TP63")
      (value "TESTPOINT")
      (footprint "eagle-import:TP_P76H50")
      (libsource (lib "eagle-import") (part "TESTPOINT"))
    )
    (comp (ref "U1")
      (value "SIP2100DY-T1-GE3")
      (footprint "eagle-import:SOIC8P127_490X600X175L71X43N_SIP2100DY-T1-GE3")
      (libsource (lib "eagle-import") (part "SIP2100DY-T1-GE3"))
    )
    (comp (ref "U2")
      (value "SIP2100DY-T1-GE3")
      (footprint "eagle-import:SOIC8P127_490X600X175L71X43N_SIP2100DY-T1-GE3")
      (libsource (lib "eagle-import") (part "SIP2100DY-T1-GE3"))
    )
    (comp (ref "U3")
      (value "SIP2100DY-T1-GE3")
      (footprint "eagle-import:SOIC8P127_490X600X175L71X43N_SIP2100DY-T1-GE3")
      (libsource (lib "eagle-import") (part "SIP2100DY-T1-GE3"))
    )
    (comp (ref "U8")
      (value "TSV991AILT")
      (footprint "eagle-import:SOT95P280X145-5N")
      (libsource (lib "eagle-import") (part "TSV991AILT"))
    )
    (comp (ref "U12")
      (value "TSV991AILT")
      (footprint "eagle-import:SOT95P280X145-5N")
      (libsource (lib "eagle-import") (part "TSV991AILT"))
    )
    (comp (ref "U19")
      (value "TSV991AILT")
      (footprint "eagle-import:SOT95P280X145-5N")
      (libsource (lib "eagle-import") (part "TSV991AILT"))
    )
    (comp (ref "C11")
      (value "0.1u")
      (footprint "eagle-import:C0603")
      (libsource (lib "eagle-import") (part "C-EUC0603"))
    )
    (comp (ref "C12")
      (value "1u")
      (footprint "eagle-import:C0603")
      (libsource (lib "eagle-import") (part "C-EUC0603"))
    )
    (comp (ref "C19")
      (value "0.033u")
      (footprint "eagle-import:C0603")
      (libsource (lib "eagle-import") (part "C-EUC0603"))
    )
    (comp (ref "C20")
      (value "0.1u")
      (footprint "eagle-import:C0603")
      (libsource (lib "eagle-import") (part "C-EUC0603"))
    )
    (comp (ref "C28")
      (value "2.2u")
      (footprint "eagle-import:C0603")
      (libsource (lib "eagle-import") (part "C-EUC0603"))
    )
    (comp (ref "C30")
      (value "10u")
      (footprint "eagle-import:C0603")
      (libsource (lib "eagle-import") (part "C-EUC0603"))
    )
    (comp (ref "C31")
      (value "0.056u")
      (footprint "eagle-import:C0603")
      (libsource (lib "eagle-import") (part "C-EUC0603"))
    )
    (comp (ref "C32")
      (value "1u")
      (footprint "eagle-import:C0603")
      (libsource (lib "eagle-import") (part "C-EUC0603"))
    )
    (comp (ref "C34")
      (value "0.1u")
      (footprint "eagle-import:C0603")
      (libsource (lib "eagle-import") (part "C-EUC0603"))
    )
    (comp (ref "J2")
      (value "TE_1-84953-1")
      (footprint "eagle-import:TE_1-84953-1")
      (libsource (lib "eagle-import") (part "TE_1-84953-1"))
    )
    (comp (ref "J3")
      (value "PINHD-1X3")
      (footprint "eagle-import:1X03")
      (libsource (lib "eagle-import") (part "PINHD-1X3"))
    )
    (comp (ref "R59")
      (value "10K")
      (footprint "eagle-import:R0603")
      (libsource (lib "eagle-import") (part "R-US_R0603"))
    )
    (comp (ref "R60")
      (value "10K")
      (footprint "eagle-import:R0603")
      (libsource (lib "eagle-import") (part "R-US_R0603"))
    )
    (comp (ref "R61")
      (value "27K")
      (footprint "eagle-import:R0603")
      (libsource (lib "eagle-import") (part "R-US_R0603"))
    )
    (comp (ref "R62")
      (value "3.3k")
      (footprint "eagle-import:R0603")
      (libsource (lib "eagle-import") (part "R-US_R0603"))
    )
    (comp (ref "R63")
      (value "3.3k")
      (footprint "eagle-import:R0603")
      (libsource (lib "eagle-import") (part "R-US_R0603"))
    )
    (comp (ref "R64")
      (value "4.7k")
      (footprint "eagle-import:R0402")
      (libsource (lib "eagle-import") (part "R-US_R0402"))
    )
    (comp (ref "R65")
      (value "4.7k")
      (footprint "eagle-import:R0402")
      (libsource (lib "eagle-import") (part "R-US_R0402"))
    )
    (comp (ref "R66")
      (value "4.7k")
      (footprint "eagle-import:R0402")
      (libsource (lib "eagle-import") (part "R-US_R0402"))
    )
    (comp (ref "R67")
      (value "5.1M")
      (footprint "eagle-import:R0402")
      (libsource (lib "eagle-import") (part "R-US_R0402"))
    )
    (comp (ref "R68")
      (value "5.1M")
      (footprint "eagle-import:R0402")
      (libsource (lib "eagle-import") (part "R-US_R0402"))
    )
    (comp (ref "R69")
      (value "5.1M")
      (footprint "eagle-import:R0402")
      (libsource (lib "eagle-import") (part "R-US_R0402"))
    )
    (comp (ref "R70")
      (value "5.1M")
      (footprint "eagle-import:R0402")
      (libsource (lib "eagle-import") (part "R-US_R0402"))
    )
    (comp (ref "R71")
      (value "5.1M")
      (footprint "eagle-import:R0402")
      (libsource (lib "eagle-import") (part "R-US_R0402"))
    )
    (comp (ref "R75")
      (value "5.1M")
      (footprint "eagle-import:R0402")
      (libsource (lib "eagle-import") (part "R-US_R0402"))
    )
    (comp (ref "R77")
      (value "10k")
      (footprint "eagle-import:R0603")
      (libsource (lib "eagle-import") (part "R-US_R0603"))
    )
    (comp (ref "R78")
      (value "2k")
      (footprint "eagle-import:R0603")
      (libsource (lib "eagle-import") (part "R-US_R0603"))
    )
    (comp (ref "R79")
      (value "1k")
      (footprint "eagle-import:R0603")
      (libsource (lib "eagle-import") (part "R-US_R0603"))
    )
    (comp (ref "R80")
      (value "100k")
      (footprint "eagle-import:R0603")
      (libsource (lib "eagle-import") (part "R-US_R0603"))
    )
    (comp (ref "RWZ")
      (value "REACTION_WHEEL_NOPINS_MAXON")
      (footprint "eagle-import:RWA_NOPINS")
      (libsource (lib "eagle-import") (part "REACTION_WHEEL_NOPINS_MAXON"))
    )
    (comp (ref "TP18")
      (value "TESTPOINT")
      (footprint "eagle-import:TP_P76H50")
      (libsource (lib "eagle-import") (part "TESTPOINT"))
    )
    (comp (ref "TP19")
      (value "TESTPOINT")
      (footprint "eagle-import:TP_P76H50")
      (libsource (lib "eagle-import") (part "TESTPOINT"))
    )
    (comp (ref "TP20")
      (value "TESTPOINT")
      (footprint "eagle-import:TP_P76H50")
      (libsource (lib "eagle-import") (part "TESTPOINT"))
    )
    (comp (ref "TP26")
      (value "TESTPOINT")
      (footprint "eagle-import:TP_P76H50")
      (libsource (lib "eagle-import") (part "TESTPOINT"))
    )
    (comp (ref "TP27")
      (value "TESTPOINT")
      (footprint "eagle-import:TP_P76H50")
      (libsource (lib "eagle-import") (part "TESTPOINT"))
    )
    (comp (ref "TP28")
      (value "TESTPOINT")
      (footprint "eagle-import:TP_P76H50")
      (libsource (lib "eagle-import") (part "TESTPOINT"))
    )
    (comp (ref "TP29")
      (value "TESTPOINT")
      (footprint "eagle-import:TP_P76H50")
      (libsource (lib "eagle-import") (part "TESTPOINT"))
    )
    (comp (ref "TP33")
      (value "TESTPOINT")
      (footprint "eagle-import:TP_P76H50")
      (libsource (lib "eagle-import") (part "TESTPOINT"))
    )
    (comp (ref "TP37")
      (value "TESTPOINT")
      (footprint "eagle-import:TP_P76H50")
      (libsource (lib "eagle-import") (part "TESTPOINT"))
    )
    (comp (ref "TP38")
      (value "TESTPOINT")
      (footprint "eagle-import:TP_P76H50")
      (libsource (lib "eagle-import") (part "TESTPOINT"))
    )
    (comp (ref "U6")
      (value "DRV10970_MOTOR_DRIVERDRV10970")
      (footprint "eagle-import:SOP65P640X120-25T240X328N")
      (libsource (lib "eagle-import") (part "DRV10970_MOTOR_DRIVERDRV10970"))
    )
    (comp (ref "U13")
      (value "LM2917MX/NOPB")
      (footprint "eagle-import:SOIC14P127_865X600X175L83X41N_LM2917MX-NOPB")
      (libsource (lib "eagle-import") (part "LM2917MX/NOPB"))
    )
    (comp (ref "C13")
      (value "0.1u")
      (footprint "eagle-import:C0603")
      (libsource (lib "eagle-import") (part "C-EUC0603"))
    )
    (comp (ref "C14")
      (value "1u")
      (footprint "eagle-import:C0603")
      (libsource (lib "eagle-import") (part "C-EUC0603"))
    )
    (comp (ref "C15")
      (value "0.033u")
      (footprint "eagle-import:C0603")
      (libsource (lib "eagle-import") (part "C-EUC0603"))
    )
    (comp (ref "C16")
      (value "0.1u")
      (footprint "eagle-import:C0603")
      (libsource (lib "eagle-import") (part "C-EUC0603"))
    )
    (comp (ref "C35")
      (value "2.2u")
      (footprint "eagle-import:C0603")
      (libsource (lib "eagle-import") (part "C-EUC0603"))
    )
    (comp (ref "C36")
      (value "10u")
      (footprint "eagle-import:C0603")
      (libsource (lib "eagle-import") (part "C-EUC0603"))
    )
    (comp (ref "C38")
      (value "0.056u")
      (footprint "eagle-import:C0603")
      (libsource (lib "eagle-import") (part "C-EUC0603"))
    )
    (comp (ref "C41")
      (value "1u")
      (footprint "eagle-import:C0603")
      (libsource (lib "eagle-import") (part "C-EUC0603"))
    )
    (comp (ref "C42")
      (value "0.1u")
      (footprint "eagle-import:C0603")
      (libsource (lib "eagle-import") (part "C-EUC0603"))
    )
    (comp (ref "J4")
      (value "TE_1-84953-1")
      (footprint "eagle-import:TE_1-84953-1")
      (libsource (lib "eagle-import") (part "TE_1-84953-1"))
    )
    (comp (ref "J6")
      (value "PINHD-1X3")
      (footprint "eagle-import:1X03")
      (libsource (lib "eagle-import") (part "PINHD-1X3"))
    )
    (comp (ref "R1")
      (value "10K")
      (footprint "eagle-import:R0603")
      (libsource (lib "eagle-import") (part "R-US_R0603"))
    )
    (comp (ref "R2")
      (value "10K")
      (footprint "eagle-import:R0603")
      (libsource (lib "eagle-import") (part "R-US_R0603"))
    )
    (comp (ref "R7")
      (value "27K")
      (footprint "eagle-import:R0603")
      (libsource (lib "eagle-import") (part "R-US_R0603"))
    )
    (comp (ref "R8")
      (value "3.3k")
      (footprint "eagle-import:R0603")
      (libsource (lib "eagle-import") (part "R-US_R0603"))
    )
    (comp (ref "R9")
      (value "3.3k")
      (footprint "eagle-import:R0603")
      (libsource (lib "eagle-import") (part "R-US_R0603"))
    )
    (comp (ref "R10")
      (value "4.7k")
      (footprint "eagle-import:R0402")
      (libsource (lib "eagle-import") (part "R-US_R0402"))
    )
    (comp (ref "R19")
      (value "4.7k")
      (footprint "eagle-import:R0402")
      (libsource (lib "eagle-import") (part "R-US_R0402"))
    )
    (comp (ref "R20")
      (value "4.7k")
      (footprint "eagle-import:R0402")
      (libsource (lib "eagle-import") (part "R-US_R0402"))
    )
    (comp (ref "R21")
      (value "5.1M")
      (footprint "eagle-import:R0402")
      (libsource (lib "eagle-import") (part "R-US_R0402"))
    )
    (comp (ref "R35")
      (value "5.1M")
      (footprint "eagle-import:R0402")
      (libsource (lib "eagle-import") (part "R-US_R0402"))
    )
    (comp (ref "R36")
      (value "5.1M")
      (footprint "eagle-import:R0402")
      (libsource (lib "eagle-import") (part "R-US_R0402"))
    )
    (comp (ref "R39")
      (value "5.1M")
      (footprint "eagle-import:R0402")
      (libsource (lib "eagle-import") (part "R-US_R0402"))
    )
    (comp (ref "R40")
      (value "5.1M")
      (footprint "eagle-import:R0402")
      (libsource (lib "eagle-import") (part "R-US_R0402"))
    )
    (comp (ref "R43")
      (value "5.1M")
      (footprint "eagle-import:R0402")
      (libsource (lib "eagle-import") (part "R-US_R0402"))
    )
    (comp (ref "R44")
      (value "10k")
      (footprint "eagle-import:R0603")
      (libsource (lib "eagle-import") (part "R-US_R0603"))
    )
    (comp (ref "R48")
      (value "2k")
      (footprint "eagle-import:R0603")
      (libsource (lib "eagle-import") (part "R-US_R0603"))
    )
    (comp (ref "R49")
      (value "1k")
      (footprint "eagle-import:R0603")
      (libsource (lib "eagle-import") (part "R-US_R0603"))
    )
    (comp (ref "R72")
      (value "100k")
      (footprint "eagle-import:R0603")
      (libsource (lib "eagle-import") (part "R-US_R0603"))
    )
    (comp (ref "TP2")
      (value "TESTPOINT")
      (footprint "eagle-import:TP_P76H50")
      (libsource (lib "eagle-import") (part "TESTPOINT"))
    )
    (comp (ref "TP4")
      (value "TESTPOINT")
      (footprint "eagle-import:TP_P76H50")
      (libsource (lib "eagle-import") (part "TESTPOINT"))
    )
    (comp (ref "TP5")
      (value "TESTPOINT")
      (footprint "eagle-import:TP_P76H50")
      (libsource (lib "eagle-import") (part "TESTPOINT"))
    )
    (comp (ref "TP11")
      (value "TESTPOINT")
      (footprint "eagle-import:TP_P76H50")
      (libsource (lib "eagle-import") (part "TESTPOINT"))
    )
    (comp (ref "TP12")
      (value "TESTPOINT")
      (footprint "eagle-import:TP_P76H50")
      (libsource (lib "eagle-import") (part "TESTPOINT"))
    )
    (comp (ref "TP13")
      (value "TESTPOINT")
      (footprint "eagle-import:TP_P76H50")
      (libsource (lib "eagle-import") (part "TESTPOINT"))
    )
    (comp (ref "TP14")
      (value "TESTPOINT")
      (footprint "eagle-import:TP_P76H50")
      (libsource (lib "eagle-import") (part "TESTPOINT"))
    )
    (comp (ref "TP15")
      (value "TESTPOINT")
      (footprint "eagle-import:TP_P76H50")
      (libsource (lib "eagle-import") (part "TESTPOINT"))
    )
    (comp (ref "TP16")
      (value "TESTPOINT")
      (footprint "eagle-import:TP_P76H50")
      (libsource (lib "eagle-import") (part "TESTPOINT"))
    )
    (comp (ref "TP23")
      (value "TESTPOINT")
      (footprint "eagle-import:TP_P76H50")
      (libsource (lib "eagle-import") (part "TESTPOINT"))
    )
    (comp (ref "U7")
      (value "DRV10970_MOTOR_DRIVERDRV10970")
      (footprint "eagle-import:SOP65P640X120-25T240X328N")
      (libsource (lib "eagle-import") (part "DRV10970_MOTOR_DRIVERDRV10970"))
    )
    (comp (ref "U10")
      (value "LM2917MX/NOPB")
      (footprint "eagle-import:SOIC14P127_865X600X175L83X41N_LM2917MX-NOPB")
      (libsource (lib "eagle-import") (part "LM2917MX/NOPB"))
    )
    (comp (ref "C54")
      (value "0.1u")
      (footprint "eagle-import:C0603")
      (libsource (lib "eagle-import") (part "C-EUC0603"))
    )
    (comp (ref "C55")
      (value "1u")
      (footprint "eagle-import:C0603")
      (libsource (lib "eagle-import") (part "C-EUC0603"))
    )
    (comp (ref "C57")
      (value "0.033u")
      (footprint "eagle-import:C0603")
      (libsource (lib "eagle-import") (part "C-EUC0603"))
    )
    (comp (ref "C58")
      (value "0.1u")
      (footprint "eagle-import:C0603")
      (libsource (lib "eagle-import") (part "C-EUC0603"))
    )
    (comp (ref "C59")
      (value "2.2u")
      (footprint "eagle-import:C0603")
      (libsource (lib "eagle-import") (part "C-EUC0603"))
    )
    (comp (ref "C60")
      (value "10u")
      (footprint "eagle-import:C0603")
      (libsource (lib "eagle-import") (part "C-EUC0603"))
    )
    (comp (ref "C61")
      (value "0.056u")
      (footprint "eagle-import:C0603")
      (libsource (lib "eagle-import") (part "C-EUC0603"))
    )
    (comp (ref "C62")
      (value "1u")
      (footprint "eagle-import:C0603")
      (libsource (lib "eagle-import") (part "C-EUC0603"))
    )
    (comp (ref "C63")
      (value "0.1u")
      (footprint "eagle-import:C0603")
      (libsource (lib "eagle-import") (part "C-EUC0603"))
    )
    (comp (ref "J11")
      (value "TE_1-84953-1")
      (footprint "eagle-import:TE_1-84953-1")
      (libsource (lib "eagle-import") (part "TE_1-84953-1"))
    )
    (comp (ref "J12")
      (value "PINHD-1X3")
      (footprint "eagle-import:1X03")
      (libsource (lib "eagle-import") (part "PINHD-1X3"))
    )
    (comp (ref "R102")
      (value "10K")
      (footprint "eagle-import:R0603")
      (libsource (lib "eagle-import") (part "R-US_R0603"))
    )
    (comp (ref "R103")
      (value "10K")
      (footprint "eagle-import:R0603")
      (libsource (lib "eagle-import") (part "R-US_R0603"))
    )
    (comp (ref "R104")
      (value "27K")
      (footprint "eagle-import:R0603")
      (libsource (lib "eagle-import") (part "R-US_R0603"))
    )
    (comp (ref "R105")
      (value "3.3k")
      (footprint "eagle-import:R0603")
      (libsource (lib "eagle-import") (part "R-US_R0603"))
    )
    (comp (ref "R106")
      (value "3.3k")
      (footprint "eagle-import:R0603")
      (libsource (lib "eagle-import") (part "R-US_R0603"))
    )
    (comp (ref "R107")
      (value "4.7k")
      (footprint "eagle-import:R0402")
      (libsource (lib "eagle-import") (part "R-US_R0402"))
    )
    (comp (ref "R108")
      (value "4.7k")
      (footprint "eagle-import:R0402")
      (libsource (lib "eagle-import") (part "R-US_R0402"))
    )
    (comp (ref "R109")
      (value "4.7k")
      (footprint "eagle-import:R0402")
      (libsource (lib "eagle-import") (part "R-US_R0402"))
    )
    (comp (ref "R110")
      (value "5.1M")
      (footprint "eagle-import:R0402")
      (libsource (lib "eagle-import") (part "R-US_R0402"))
    )
    (comp (ref "R111")
      (value "5.1M")
      (footprint "eagle-import:R0402")
      (libsource (lib "eagle-import") (part "R-US_R0402"))
    )
    (comp (ref "R112")
      (value "5.1M")
      (footprint "eagle-import:R0402")
      (libsource (lib "eagle-import") (part "R-US_R0402"))
    )
    (comp (ref "R113")
      (value "5.1M")
      (footprint "eagle-import:R0402")
      (libsource (lib "eagle-import") (part "R-US_R0402"))
    )
    (comp (ref "R114")
      (value "5.1M")
      (footprint "eagle-import:R0402")
      (libsource (lib "eagle-import") (part "R-US_R0402"))
    )
    (comp (ref "R115")
      (value "5.1M")
      (footprint "eagle-import:R0402")
      (libsource (lib "eagle-import") (part "R-US_R0402"))
    )
    (comp (ref "R116")
      (value "10k")
      (footprint "eagle-import:R0603")
      (libsource (lib "eagle-import") (part "R-US_R0603"))
    )
    (comp (ref "R117")
      (value "2k")
      (footprint "eagle-import:R0603")
      (libsource (lib "eagle-import") (part "R-US_R0603"))
    )
    (comp (ref "R118")
      (value "1k")
      (footprint "eagle-import:R0603")
      (libsource (lib "eagle-import") (part "R-US_R0603"))
    )
    (comp (ref "R119")
      (value "100k")
      (footprint "eagle-import:R0603")
      (libsource (lib "eagle-import") (part "R-US_R0603"))
    )
    (comp (ref "TP49")
      (value "TESTPOINT")
      (footprint "eagle-import:TP_P76H50")
      (libsource (lib "eagle-import") (part "TESTPOINT"))
    )
    (comp (ref "TP50")
      (value "TESTPOINT")
      (footprint "eagle-import:TP_P76H50")
      (libsource (lib "eagle-import") (part "TESTPOINT"))
    )
    (comp (ref "TP53")
      (value "TESTPOINT")
      (footprint "eagle-import:TP_P76H50")
      (libsource (lib "eagle-import") (part "TESTPOINT"))
    )
    (comp (ref "TP55")
      (value "TESTPOINT")
      (footprint "eagle-import:TP_P76H50")
      (libsource (lib "eagle-import") (part "TESTPOINT"))
    )
    (comp (ref "TP56")
      (value "TESTPOINT")
      (footprint "eagle-import:TP_P76H50")
      (libsource (lib "eagle-import") (part "TESTPOINT"))
    )
    (comp (ref "TP57")
      (value "TESTPOINT")
      (footprint "eagle-import:TP_P76H50")
      (libsource (lib "eagle-import") (part "TESTPOINT"))
    )
    (comp (ref "TP58")
      (value "TESTPOINT")
      (footprint "eagle-import:TP_P76H50")
      (libsource (lib "eagle-import") (part "TESTPOINT"))
    )
    (comp (ref "TP59")
      (value "TESTPOINT")
      (footprint "eagle-import:TP_P76H50")
      (libsource (lib "eagle-import") (part "TESTPOINT"))
    )
    (comp (ref "TP60")
      (value "TESTPOINT")
      (footprint "eagle-import:TP_P76H50")
      (libsource (lib "eagle-import") (part "TESTPOINT"))
    )
    (comp (ref "TP61")
      (value "TESTPOINT")
      (footprint "eagle-import:TP_P76H50")
      (libsource (lib "eagle-import") (part "TESTPOINT"))
    )
    (comp (ref "U16")
      (value "DRV10970_MOTOR_DRIVERDRV10970")
      (footprint "eagle-import:SOP65P640X120-25T240X328N")
      (libsource (lib "eagle-import") (part "DRV10970_MOTOR_DRIVERDRV10970"))
    )
    (comp (ref "U17")
      (value "LM2917MX/NOPB")
      (footprint "eagle-import:SOIC14P127_865X600X175L83X41N_LM2917MX-NOPB")
      (libsource (lib "eagle-import") (part "LM2917MX/NOPB"))
    )
    (comp (ref "C72")
      (value "0.1u")
      (footprint "eagle-import:C0402")
      (libsource (lib "eagle-import") (part "C-EUC0402"))
    )
    (comp (ref "C73")
      (value "1u")
      (footprint "eagle-import:C0402")
      (libsource (lib "eagle-import") (part "C-EUC0402"))
    )
    (comp (ref "C74")
      (value "0.1u")
      (footprint "eagle-import:C0402")
      (libsource (lib "eagle-import") (part "C-EUC0402"))
    )
    (comp (ref "C75")
      (value "1u")
      (footprint "eagle-import:C0402")
      (libsource (lib "eagle-import") (part "C-EUC0402"))
    )
    (comp (ref "C76")
      (value "0.1u")
      (footprint "eagle-import:C0402")
      (libsource (lib "eagle-import") (part "C-EUC0402"))
    )
    (comp (ref "C77")
      (value "1u")
      (footprint "eagle-import:C0402")
      (libsource (lib "eagle-import") (part "C-EUC0402"))
    )
    (comp (ref "C78")
      (value "0.1u")
      (footprint "eagle-import:C0402")
      (libsource (lib "eagle-import") (part "C-EUC0402"))
    )
    (comp (ref "C86")
      (value "0.1u")
      (footprint "eagle-import:C0402")
      (libsource (lib "eagle-import") (part "C-EUC0402"))
    )
    (comp (ref "C87")
      (value "1u")
      (footprint "eagle-import:C0402")
      (libsource (lib "eagle-import") (part "C-EUC0402"))
    )
    (comp (ref "C88")
      (value "0.1u")
      (footprint "eagle-import:C0402")
      (libsource (lib "eagle-import") (part "C-EUC0402"))
    )
    (comp (ref "C89")
      (value "1u")
      (footprint "eagle-import:C0402")
      (libsource (lib "eagle-import") (part "C-EUC0402"))
    )
    (comp (ref "C90")
      (value "0.1u")
      (footprint "eagle-import:C0402")
      (libsource (lib "eagle-import") (part "C-EUC0402"))
    )
    (comp (ref "C91")
      (value "1u")
      (footprint "eagle-import:C0402")
      (libsource (lib "eagle-import") (part "C-EUC0402"))
    )
    (comp (ref "C92")
      (value "0.1u")
      (footprint "eagle-import:C0402")
      (libsource (lib "eagle-import") (part "C-EUC0402"))
    )
    (comp (ref "R4")
      (value "5.1M")
      (footprint "eagle-import:R0402")
      (libsource (lib "eagle-import") (part "R-US_R0402"))
    )
    (comp (ref "R13")
      (value "5.1M")
      (footprint "eagle-import:R0402")
      (libsource (lib "eagle-import") (part "R-US_R0402"))
    )
    (comp (ref "R29")
      (value "10K")
      (footprint "eagle-import:R0402")
      (libsource (lib "eagle-import") (part "R-US_R0402"))
    )
    (comp (ref "R37")
      (value "5.1M")
      (footprint "eagle-import:R0402")
      (libsource (lib "eagle-import") (part "R-US_R0402"))
    )
    (comp (ref "R50")
      (value "10K")
      (footprint "eagle-import:R0402")
      (libsource (lib "eagle-import") (part "R-US_R0402"))
    )
    (comp (ref "R51")
      (value "5.1M")
      (footprint "eagle-import:R0402")
      (libsource (lib "eagle-import") (part "R-US_R0402"))
    )
    (comp (ref "U14")
      (value "ADS7841E_2K5")
      (footprint "eagle-import:DBQ16")
      (fields
        (field (name "GENERIC_PART_NUMBER") "ADS7841")
        (field (name "MANUFACTURER") "Texas Instruments")
      )
      (libsource (lib "eagle-import") (part "ADS7841E_2K5"))
    )
    (comp (ref "U20")
      (value "ADS7841E_2K5")
      (footprint "eagle-import:DBQ16")
      (fields
        (field (name "GENERIC_PART_NUMBER") "ADS7841")
        (field (name "MANUFACTURER") "Texas Instruments")
      )
      (libsource (lib "eagle-import") (part "ADS7841E_2K5"))
    )
  )
  (nets
    (net (code "1") (name "+3V3") (class "Default")
      (node (ref "C34") (pin "2") (pinfunction "2_2") (pintype "passive"))
      (node (ref "C42") (pin "2") (pinfunction "2_2") (pintype "passive"))
      (node (ref "C63") (pin "2") (pinfunction "2_2") (pintype "passive"))
      (node (ref "C65") (pin "1") (pinfunction "1_1") (pintype "passive"))
      (node (ref "C66") (pin "1") (pinfunction "1_1") (pintype "passive"))
      (node (ref "C67") (pin "1") (pinfunction "1_1") (pintype "passive"))
      (node (ref "C68") (pin "1") (pinfunction "1_1") (pintype "passive"))
      (node (ref "C70") (pin "1") (pinfunction "1_1") (pintype "passive"))
      (node (ref "C71") (pin "1") (pinfunction "1_1") (pintype "passive"))
      (node (ref "C72") (pin "1") (pinfunction "1_1") (pintype "passive"))
      (node (ref "C73") (pin "1") (pinfunction "1_1") (pintype "passive"))
      (node (ref "C74") (pin "1") (pinfunction "1_1") (pintype "passive"))
      (node (ref "C75") (pin "1") (pinfunction "1_1") (pintype "passive"))
      (node (ref "C77") (pin "1") (pinfunction "1_1") (pintype "passive"))
      (node (ref "C78") (pin "1") (pinfunction "1_1") (pintype "passive"))
      (node (ref "C86") (pin "1") (pinfunction "1_1") (pintype "passive"))
      (node (ref "C87") (pin "1") (pinfunction "1_1") (pintype "passive"))
      (node (ref "C88") (pin "1") (pinfunction "1_1") (pintype "passive"))
      (node (ref "C89") (pin "1") (pinfunction "1_1") (pintype "passive"))
      (node (ref "C91") (pin "1") (pinfunction "1_1") (pintype "passive"))
      (node (ref "C92") (pin "1") (pinfunction "1_1") (pintype "passive"))
      (node (ref "J1") (pin "2") (pinfunction "2_2") (pintype "passive"))
      (node (ref "J5") (pin "2") (pinfunction "3V3_2") (pintype "bidirectional"))
      (node (ref "JP1A") (pin "1") (pinfunction "1_1") (pintype "passive"))
      (node (ref "R105") (pin "1") (pinfunction "1_1") (pintype "passive"))
      (node (ref "R106") (pin "1") (pinfunction "1_1") (pintype "passive"))
      (node (ref "R118") (pin "1") (pinfunction "1_1") (pintype "passive"))
      (node (ref "R29") (pin "2") (pinfunction "2_2") (pintype "passive"))
      (node (ref "R49") (pin "1") (pinfunction "1_1") (pintype "passive"))
      (node (ref "R5") (pin "2") (pinfunction "2_2") (pintype "passive"))
      (node (ref "R50") (pin "2") (pinfunction "2_2") (pintype "passive"))
      (node (ref "R62") (pin "1") (pinfunction "1_1") (pintype "passive"))
      (node (ref "R63") (pin "1") (pinfunction "1_1") (pintype "passive"))
      (node (ref "R79") (pin "1") (pinfunction "1_1") (pintype "passive"))
      (node (ref "R8") (pin "1") (pinfunction "1_1") (pintype "passive"))
      (node (ref "R9") (pin "1") (pinfunction "1_1") (pintype "passive"))
      (node (ref "U10") (pin "8") (pinfunction "COL_8") (pintype "bidirectional"))
      (node (ref "U10") (pin "9") (pinfunction "V+_9") (pintype "bidirectional"))
      (node (ref "U13") (pin "8") (pinfunction "COL_8") (pintype "bidirectional"))
      (node (ref "U13") (pin "9") (pinfunction "V+_9") (pintype "bidirectional"))
      (node (ref "U14") (pin "1") (pinfunction "VCC+_2_1") (pintype "power_in"))
      (node (ref "U14") (pin "8") (pinfunction "VREF_8") (pintype "input"))
      (node (ref "U14") (pin "9") (pinfunction "VCC+_9") (pintype "power_in"))
      (node (ref "U17") (pin "8") (pinfunction "COL_8") (pintype "bidirectional"))
      (node (ref "U17") (pin "9") (pinfunction "V+_9") (pintype "bidirectional"))
      (node (ref "U20") (pin "1") (pinfunction "VCC+_2_1") (pintype "power_in"))
      (node (ref "U20") (pin "8") (pinfunction "VREF_8") (pintype "input"))
      (node (ref "U20") (pin "9") (pinfunction "VCC+_9") (pintype "power_in"))
      (node (ref "U9") (pin "1") (pinfunction "VCC+_2_1") (pintype "power_in"))
      (node (ref "U9") (pin "8") (pinfunction "VREF_8") (pintype "input"))
      (node (ref "U9") (pin "9") (pinfunction "VCC+_9") (pintype "power_in"))
    )
    (net (code "2") (name "+5V") (class "Default")
      (node (ref "C1") (pin "1") (pinfunction "1_1") (pintype "passive"))
      (node (ref "C12") (pin "1") (pinfunction "1_1") (pintype "passive"))
      (node (ref "C14") (pin "1") (pinfunction "1_1") (pintype "passive"))
      (node (ref "C2") (pin "2") (pinfunction "2_2") (pintype "passive"))
      (node (ref "C3") (pin "1") (pinfunction "1_1") (pintype "passive"))
      (node (ref "C30") (pin "1") (pinfunction "1_1") (pintype "passive"))
      (node (ref "C36") (pin "1") (pinfunction "1_1") (pintype "passive"))
      (node (ref "C4") (pin "2") (pinfunction "2_2") (pintype "passive"))
      (node (ref "C46") (pin "1") (pinfunction "1_1") (pintype "passive"))
      (node (ref "C52") (pin "1") (pinfunction "1_1") (pintype "passive"))
      (node (ref "C55") (pin "1") (pinfunction "1_1") (pintype "passive"))
      (node (ref "C60") (pin "1") (pinfunction "1_1") (pintype "passive"))
      (node (ref "J1") (pin "1") (pinfunction "1_1") (pintype "passive"))
      (node (ref "J11") (pin "1") (pinfunction "1_1") (pintype "bidirectional"))
      (node (ref "J12") (pin "3") (pinfunction "3_3") (pintype "passive"))
      (node (ref "J2") (pin "1") (pinfunction "1_1") (pintype "bidirectional"))
      (node (ref "J3") (pin "3") (pinfunction "3_3") (pintype "passive"))
      (node (ref "J4") (pin "1") (pinfunction "1_1") (pintype "bidirectional"))
      (node (ref "J5") (pin "1") (pinfunction "5V_1") (pintype "bidirectional"))
      (node (ref "J6") (pin "3") (pinfunction "3_3") (pintype "passive"))
      (node (ref "JP1A") (pin "2") (pinfunction "2_2") (pintype "passive"))
      (node (ref "R1") (pin "2") (pinfunction "2_2") (pintype "passive"))
      (node (ref "R10") (pin "2") (pinfunction "2_2") (pintype "passive"))
      (node (ref "R102") (pin "2") (pinfunction "2_2") (pintype "passive"))
      (node (ref "R107") (pin "2") (pinfunction "2_2") (pintype "passive"))
      (node (ref "R108") (pin "2") (pinfunction "2_2") (pintype "passive"))
      (node (ref "R109") (pin "2") (pinfunction "2_2") (pintype "passive"))
      (node (ref "R17") (pin "2") (pinfunction "2_2") (pintype "passive"))
      (node (ref "R19") (pin "2") (pinfunction "2_2") (pintype "passive"))
      (node (ref "R20") (pin "2") (pinfunction "2_2") (pintype "passive"))
      (node (ref "R34") (pin "2") (pinfunction "2_2") (pintype "passive"))
      (node (ref "R59") (pin "2") (pinfunction "2_2") (pintype "passive"))
      (node (ref "R64") (pin "2") (pinfunction "2_2") (pintype "passive"))
      (node (ref "R65") (pin "2") (pinfunction "2_2") (pintype "passive"))
      (node (ref "R66") (pin "2") (pinfunction "2_2") (pintype "passive"))
      (node (ref "R86") (pin "2") (pinfunction "2_2") (pintype "passive"))
      (node (ref "U1") (pin "3") (pinfunction "VDD_3") (pintype "bidirectional"))
      (node (ref "U12") (pin "5") (pinfunction "VCC_5") (pintype "power_in"))
      (node (ref "U16") (pin "15") (pinfunction "VM_15") (pintype "bidirectional"))
      (node (ref "U19") (pin "5") (pinfunction "VCC_5") (pintype "power_in"))
      (node (ref "U2") (pin "3") (pinfunction "VDD_3") (pintype "bidirectional"))
      (node (ref "U3") (pin "3") (pinfunction "VDD_3") (pintype "bidirectional"))
      (node (ref "U6") (pin "15") (pinfunction "VM_15") (pintype "bidirectional"))
      (node (ref "U7") (pin "15") (pinfunction "VM_15") (pintype "bidirectional"))
      (node (ref "U8") (pin "5") (pinfunction "VCC_5") (pintype "power_in"))
    )
    (net (code "3") (name "BRKMOD_X") (class "Default")
      (node (ref "J6") (pin "2") (pinfunction "2_2") (pintype "passive"))
      (node (ref "U7") (pin "21") (pinfunction "BRKMOD_21") (pintype "bidirectional"))
    )
    (net (code "4") (name "BRKMOD_Y") (class "Default")
      (node (ref "J12") (pin "2") (pinfunction "2_2") (pintype "passive"))
      (node (ref "U16") (pin "21") (pinfunction "BRKMOD_21") (pintype "bidirectional"))
    )
    (net (code "5") (name "BRKMOD_Z") (class "Default")
      (node (ref "J3") (pin "2") (pinfunction "2_2") (pintype "passive"))
      (node (ref "U6") (pin "21") (pinfunction "BRKMOD_21") (pintype "bidirectional"))
    )
    (net (code "6") (name "CUR_OUT1") (class "Default")
      (node (ref "R16") (pin "2") (pinfunction "2_2") (pintype "passive"))
      (node (ref "TP10") (pin "1") (pinfunction "TP_1") (pintype "input"))
      (node (ref "U8") (pin "1") (pinfunction "OUT_1") (pintype "output"))
      (node (ref "U9") (pin "2") (pinfunction "CH0_2") (pintype "input"))
    )
    (net (code "7") (name "CUR_OUT2") (class "Default")
      (node (ref "R33") (pin "2") (pinfunction "2_2") (pintype "passive"))
      (node (ref "TP30") (pin "1") (pinfunction "TP_1") (pintype "input"))
      (node (ref "U12") (pin "1") (pinfunction "OUT_1") (pintype "output"))
      (node (ref "U9") (pin "3") (pinfunction "CH1_3") (pintype "input"))
    )
    (net (code "8") (name "CUR_OUT3") (class "Default")
      (node (ref "R85") (pin "2") (pinfunction "2_2") (pintype "passive"))
      (node (ref "TP51") (pin "1") (pinfunction "TP_1") (pintype "input"))
      (node (ref "U19") (pin "1") (pinfunction "OUT_1") (pintype "output"))
      (node (ref "U9") (pin "4") (pinfunction "CH2_4") (pintype "input"))
    )
    (net (code "9") (name "GND") (class "Default")
      (node (ref "C1") (pin "2") (pinfunction "2_2") (pintype "passive"))
      (node (ref "C15") (pin "2") (pinfunction "2_2") (pintype "passive"))
      (node (ref "C16") (pin "2") (pinfunction "2_2") (pintype "passive"))
      (node (ref "C19") (pin "2") (pinfunction "2_2") (pintype "passive"))
      (node (ref "C2") (pin "1") (pinfunction "1_1") (pintype "passive"))
      (node (ref "C20") (pin "2") (pinfunction "2_2") (pintype "passive"))
      (node (ref "C28") (pin "2") (pinfunction "2_2") (pintype "passive"))
      (node (ref "C3") (pin "2") (pinfunction "2_2") (pintype "passive"))
      (node (ref "C30") (pin "2") (pinfunction "2_2") (pintype "passive"))
      (node (ref "C31") (pin "1") (pinfunction "1_1") (pintype "passive"))
      (node (ref "C32") (pin "1") (pinfunction "1_1") (pintype "passive"))
      (node (ref "C34") (pin "1") (pinfunction "1_1") (pintype "passive"))
      (node (ref "C35") (pin "2") (pinfunction "2_2") (pintype "passive"))
      (node (ref "C36") (pin "2") (pinfunction "2_2") (pintype "passive"))
      (node (ref "C38") (pin "1") (pinfunction "1_1") (pintype "passive"))
      (node (ref "C4") (pin "1") (pinfunction "1_1") (pintype "passive"))
      (node (ref "C41") (pin "1") (pinfunction "1_1") (pintype "passive"))
      (node (ref "C42") (pin "1") (pinfunction "1_1") (pintype "passive"))
      (node (ref "C46") (pin "2") (pinfunction "2_2") (pintype "passive"))
      (node (ref "C52") (pin "2") (pinfunction "2_2") (pintype "passive"))
      (node (ref "C57") (pin "2") (pinfunction "2_2") (pintype "passive"))
      (node (ref "C58") (pin "2") (pinfunction "2_2") (pintype "passive"))
      (node (ref "C59") (pin "2") (pinfunction "2_2") (pintype "passive"))
      (node (ref "C60") (pin "2") (pinfunction "2_2") (pintype "passive"))
      (node (ref "C61") (pin "1") (pinfunction "1_1") (pintype "passive"))
      (node (ref "C62") (pin "1") (pinfunction "1_1") (pintype "passive"))
      (node (ref "C63") (pin "1") (pinfunction "1_1") (pintype "passive"))
      (node (ref "C65") (pin "2") (pinfunction "2_2") (pintype "passive"))
      (node (ref "C66") (pin "2") (pinfunction "2_2") (pintype "passive"))
      (node (ref "C67") (pin "2") (pinfunction "2_2") (pintype "passive"))
      (node (ref "C68") (pin "2") (pinfunction "2_2") (pintype "passive"))
      (node (ref "C69") (pin "2") (pinfunction "2_2") (pintype "passive"))
      (node (ref "C70") (pin "2") (pinfunction "2_2") (pintype "passive"))
      (node (ref "C71") (pin "2") (pinfunction "2_2") (pintype "passive"))
      (node (ref "C72") (pin "2") (pinfunction "2_2") (pintype "passive"))
      (node (ref "C73") (pin "2") (pinfunction "2_2") (pintype "passive"))
      (node (ref "C74") (pin "2") (pinfunction "2_2") (pintype "passive"))
      (node (ref "C75") (pin "2") (pinfunction "2_2") (pintype "passive"))
      (node (ref "C76") (pin "2") (pinfunction "2_2") (pintype "passive"))
      (node (ref "C77") (pin "2") (pinfunction "2_2") (pintype "passive"))
      (node (ref "C78") (pin "2") (pinfunction "2_2") (pintype "passive"))
      (node (ref "C86") (pin "2") (pinfunction "2_2") (pintype "passive"))
      (node (ref "C87") (pin "2") (pinfunction "2_2") (pintype "passive"))
      (node (ref "C88") (pin "2") (pinfunction "2_2") (pintype "passive"))
      (node (ref "C89") (pin "2") (pinfunction "2_2") (pintype "passive"))
      (node (ref "C90") (pin "2") (pinfunction "2_2") (pintype "passive"))
      (node (ref "C91") (pin "2") (pinfunction "2_2") (pintype "passive"))
      (node (ref "C92") (pin "2") (pinfunction "2_2") (pintype "passive"))
      (node (ref "J1") (pin "3") (pinfunction "3_3") (pintype "passive"))
      (node (ref "J11") (pin "5") (pinfunction "5_5") (pintype "bidirectional"))
      (node (ref "J11") (pin "TAB1") (pinfunction "TAB1_TAB1") (pintype "bidirectional"))
      (node (ref "J11") (pin "TAB2") (pinfunction "TAB2_TAB2") (pintype "bidirectional"))
      (node (ref "J12") (pin "1") (pinfunction "1_1") (pintype "passive"))
      (node (ref "J2") (pin "5") (pinfunction "5_5") (pintype "bidirectional"))
      (node (ref "J2") (pin "TAB1") (pinfunction "TAB1_TAB1") (pintype "bidirectional"))
      (node (ref "J2") (pin "TAB2") (pinfunction "TAB2_TAB2") (pintype "bidirectional"))
      (node (ref "J3") (pin "1") (pinfunction "1_1") (pintype "passive"))
      (node (ref "J4") (pin "5") (pinfunction "5_5") (pintype "bidirectional"))
      (node (ref "J4") (pin "TAB1") (pinfunction "TAB1_TAB1") (pintype "bidirectional"))
      (node (ref "J4") (pin "TAB2") (pinfunction "TAB2_TAB2") (pintype "bidirectional"))
      (node (ref "J5") (pin "3") (pinfunction "GND_3") (pintype "bidirectional"))
      (node (ref "J6") (pin "1") (pinfunction "1_1") (pintype "passive"))
      (node (ref "R103") (pin "1") (pinfunction "1_1") (pintype "passive"))
      (node (ref "R104") (pin "1") (pinfunction "1_1") (pintype "passive"))
      (node (ref "R110") (pin "1") (pinfunction "1_1") (pintype "passive"))
      (node (ref "R111") (pin "2") (pinfunction "2_2") (pintype "passive"))
      (node (ref "R112") (pin "2") (pinfunction "2_2") (pintype "passive"))
      (node (ref "R113") (pin "2") (pinfunction "2_2") (pintype "passive"))
      (node (ref "R114") (pin "2") (pinfunction "2_2") (pintype "passive"))
      (node (ref "R115") (pin "2") (pinfunction "2_2") (pintype "passive"))
      (node (ref "R116") (pin "1") (pinfunction "1_1") (pintype "passive"))
      (node (ref "R117") (pin "2") (pinfunction "2_2") (pintype "passive"))
      (node (ref "R119") (pin "1") (pinfunction "1_1") (pintype "passive"))
      (node (ref "R13") (pin "2") (pinfunction "2_2") (pintype "passive"))
      (node (ref "R14") (pin "2") (pinfunction "2_2") (pintype "passive"))
      (node (ref "R18") (pin "1") (pinfunction "1_1") (pintype "passive"))
      (node (ref "R2") (pin "1") (pinfunction "1_1") (pintype "passive"))
      (node (ref "R21") (pin "1") (pinfunction "1_1") (pintype "passive"))
      (node (ref "R23") (pin "1") (pinfunction "1_1") (pintype "passive"))
      (node (ref "R3") (pin "1") (pinfunction "1_1") (pintype "passive"))
      (node (ref "R35") (pin "2") (pinfunction "2_2") (pintype "passive"))
      (node (ref "R36") (pin "2") (pinfunction "2_2") (pintype "passive"))
      (node (ref "R37") (pin "1") (pinfunction "1_1") (pintype "passive"))
      (node (ref "R39") (pin "2") (pinfunction "2_2") (pintype "passive"))
      (node (ref "R4") (pin "2") (pinfunction "2_2") (pintype "passive"))
      (node (ref "R40") (pin "2") (pinfunction "2_2") (pintype "passive"))
      (node (ref "R41") (pin "1") (pinfunction "1_1") (pintype "passive"))
      (node (ref "R43") (pin "2") (pinfunction "2_2") (pintype "passive"))
      (node (ref "R44") (pin "1") (pinfunction "1_1") (pintype "passive"))
      (node (ref "R48") (pin "2") (pinfunction "2_2") (pintype "passive"))
      (node (ref "R51") (pin "1") (pinfunction "1_1") (pintype "passive"))
      (node (ref "R60") (pin "1") (pinfunction "1_1") (pintype "passive"))
      (node (ref "R61") (pin "1") (pinfunction "1_1") (pintype "passive"))
      (node (ref "R67") (pin "1") (pinfunction "1_1") (pintype "passive"))
      (node (ref "R68") (pin "2") (pinfunction "2_2") (pintype "passive"))
      (node (ref "R69") (pin "2") (pinfunction "2_2") (pintype "passive"))
      (node (ref "R7") (pin "1") (pinfunction "1_1") (pintype "passive"))
      (node (ref "R70") (pin "2") (pinfunction "2_2") (pintype "passive"))
      (node (ref "R71") (pin "2") (pinfunction "2_2") (pintype "passive"))
      (node (ref "R72") (pin "1") (pinfunction "1_1") (pintype "passive"))
      (node (ref "R75") (pin "2") (pinfunction "2_2") (pintype "passive"))
      (node (ref "R77") (pin "1") (pinfunction "1_1") (pintype "passive"))
      (node (ref "R78") (pin "2") (pinfunction "2_2") (pintype "passive"))
      (node (ref "R80") (pin "1") (pinfunction "1_1") (pintype "passive"))
      (node (ref "R87") (pin "1") (pinfunction "1_1") (pintype "passive"))
      (node (ref "U1") (pin "1") (pinfunction "SA_1") (pintype "bidirectional"))
      (node (ref "U1") (pin "2") (pinfunction "GND_2") (pintype "bidirectional"))
      (node (ref "U1") (pin "4") (pinfunction "SB_4") (pintype "bidirectional"))
      (node (ref "U10") (pin "12") (pinfunction "GND_12") (pintype "bidirectional"))
      (node (ref "U12") (pin "2") (pinfunction "VSS_2") (pintype "power_in"))
      (node (ref "U13") (pin "12") (pinfunction "GND_12") (pintype "bidirectional"))
      (node (ref "U14") (pin "10") (pinfunction "GND_10") (pintype "power_in"))
      (node (ref "U14") (pin "11") (pinfunction "MODE_11") (pintype "passive"))
      (node (ref "U14") (pin "6") (pinfunction "COM_6") (pintype "input"))
      (node (ref "U16") (pin "12") (pinfunction "GND_12") (pintype "bidirectional"))
      (node (ref "U16") (pin "25") (pinfunction "THERMALPAD_25") (pintype "bidirectional"))
      (node (ref "U17") (pin "12") (pinfunction "GND_12") (pintype "bidirectional"))
      (node (ref "U19") (pin "2") (pinfunction "VSS_2") (pintype "power_in"))
      (node (ref "U2") (pin "1") (pinfunction "SA_1") (pintype "bidirectional"))
      (node (ref "U2") (pin "2") (pinfunction "GND_2") (pintype "bidirectional"))
      (node (ref "U2") (pin "4") (pinfunction "SB_4") (pintype "bidirectional"))
      (node (ref "U20") (pin "10") (pinfunction "GND_10") (pintype "power_in"))
      (node (ref "U20") (pin "11") (pinfunction "MODE_11") (pintype "passive"))
      (node (ref "U20") (pin "6") (pinfunction "COM_6") (pintype "input"))
      (node (ref "U3") (pin "1") (pinfunction "SA_1") (pintype "bidirectional"))
      (node (ref "U3") (pin "2") (pinfunction "GND_2") (pintype "bidirectional"))
      (node (ref "U3") (pin "4") (pinfunction "SB_4") (pintype "bidirectional"))
      (node (ref "U6") (pin "12") (pinfunction "GND_12") (pintype "bidirectional"))
      (node (ref "U6") (pin "25") (pinfunction "THERMALPAD_25") (pintype "bidirectional"))
      (node (ref "U7") (pin "12") (pinfunction "GND_12") (pintype "bidirectional"))
      (node (ref "U7") (pin "25") (pinfunction "THERMALPAD_25") (pintype "bidirectional"))
      (node (ref "U8") (pin "2") (pinfunction "VSS_2") (pintype "power_in"))
      (node (ref "U9") (pin "10") (pinfunction "GND_10") (pintype "power_in"))
      (node (ref "U9") (pin "11") (pinfunction "MODE_11") (pintype "passive"))
      (node (ref "U9") (pin "6") (pinfunction "COM_6") (pintype "input"))
    )
    (net (code "10") (name "MAG_CUR_SEN_X") (class "Default")
      (node (ref "R24") (pin "2") (pinfunction "2_2") (pintype "passive"))
      (node (ref "R6") (pin "2") (pinfunction "2_2") (pintype "passive"))
      (node (ref "TP17") (pin "1") (pinfunction "TP_1") (pintype "input"))
      (node (ref "U1") (pin "8") (pinfunction "OUTA_8") (pintype "bidirectional"))
    )
    (net (code "11") (name "MAG_CUR_SEN_Y") (class "Default")
      (node (ref "R25") (pin "2") (pinfunction "2_2") (pintype "passive"))
      (node (ref "R47") (pin "2") (pinfunction "2_2") (pintype "passive"))
      (node (ref "TP34") (pin "1") (pinfunction "TP_1") (pintype "input"))
      (node (ref "U2") (pin "8") (pinfunction "OUTA_8") (pintype "bidirectional"))
    )
    (net (code "12") (name "MAG_CUR_SEN_Z") (class "Default")
      (node (ref "R81") (pin "2") (pinfunction "2_2") (pintype "passive"))
      (node (ref "R89") (pin "2") (pinfunction "2_2") (pintype "passive"))
      (node (ref "TP52") (pin "1") (pinfunction "TP_1") (pintype "input"))
      (node (ref "U3") (pin "8") (pinfunction "OUTA_8") (pintype "bidirectional"))
    )
    (net (code "13") (name "MAG_X_FIN") (class "Default")
      (node (ref "JP1A") (pin "8") (pinfunction "8_8") (pintype "passive"))
      (node (ref "TP8") (pin "1") (pinfunction "TP_1") (pintype "input"))
      (node (ref "U1") (pin "7") (pinfunction "INA_7") (pintype "bidirectional"))
    )
    (net (code "14") (name "MAG_X_RIN") (class "Default")
      (node (ref "JP1A") (pin "6") (pinfunction "6_6") (pintype "passive"))
      (node (ref "TP9") (pin "1") (pinfunction "TP_1") (pintype "input"))
      (node (ref "U1") (pin "6") (pinfunction "INB_6") (pintype "bidirectional"))
    )
    (net (code "15") (name "MAG_Y_FIN") (class "Default")
      (node (ref "JP1A") (pin "12") (pinfunction "12_12") (pintype "passive"))
      (node (ref "TP24") (pin "1") (pinfunction "TP_1") (pintype "input"))
      (node (ref "U2") (pin "7") (pinfunction "INA_7") (pintype "bidirectional"))
    )
    (net (code "16") (name "MAG_Y_RIN") (class "Default")
      (node (ref "JP1A") (pin "10") (pinfunction "10_10") (pintype "passive"))
      (node (ref "TP25") (pin "1") (pinfunction "TP_1") (pintype "input"))
      (node (ref "U2") (pin "6") (pinfunction "INB_6") (pintype "bidirectional"))
    )
    (net (code "17") (name "MAG_Z_FIN") (class "Default")
      (node (ref "JP1B") (pin "4") (pinfunction "4_4") (pintype "passive"))
      (node (ref "TP47") (pin "1") (pinfunction "TP_1") (pintype "input"))
      (node (ref "U3") (pin "7") (pinfunction "INA_7") (pintype "bidirectional"))
    )
    (net (code "18") (name "MAG_Z_RIN") (class "Default")
      (node (ref "JP1B") (pin "2") (pinfunction "2_2") (pintype "passive"))
      (node (ref "TP48") (pin "1") (pinfunction "TP_1") (pintype "input"))
      (node (ref "U3") (pin "6") (pinfunction "INB_6") (pintype "bidirectional"))
    )
    (net (code "19") (name "Net-(JP1A-Pad4)") (class "Default")
      (node (ref "JP1A") (pin "4") (pinfunction "4_4") (pintype "passive"))
      (node (ref "R3") (pin "2") (pinfunction "2_2") (pintype "passive"))
    )
    (net (code "20") (name "Net-(R11-Pad2)") (class "Default")
      (node (ref "R11") (pin "2") (pinfunction "2_2") (pintype "passive"))
      (node (ref "R22") (pin "2") (pinfunction "2_2") (pintype "passive"))
      (node (ref "R24") (pin "1") (pinfunction "1_1") (pintype "passive"))
    )
    (net (code "21") (name "Net-(R15-Pad1)") (class "Default")
      (node (ref "R15") (pin "1") (pinfunction "1_1") (pintype "passive"))
      (node (ref "R17") (pin "1") (pinfunction "1_1") (pintype "passive"))
      (node (ref "R18") (pin "2") (pinfunction "2_2") (pintype "passive"))
    )
    (net (code "22") (name "Net-(R30-Pad2)") (class "Default")
      (node (ref "R30") (pin "2") (pinfunction "2_2") (pintype "passive"))
      (node (ref "R42") (pin "2") (pinfunction "2_2") (pintype "passive"))
      (node (ref "R47") (pin "1") (pinfunction "1_1") (pintype "passive"))
    )
    (net (code "23") (name "Net-(R32-Pad1)") (class "Default")
      (node (ref "R32") (pin "1") (pinfunction "1_1") (pintype "passive"))
      (node (ref "R34") (pin "1") (pinfunction "1_1") (pintype "passive"))
      (node (ref "R41") (pin "2") (pinfunction "2_2") (pintype "passive"))
    )
    (net (code "24") (name "Net-(R82-Pad2)") (class "Default")
      (node (ref "R82") (pin "2") (pinfunction "2_2") (pintype "passive"))
      (node (ref "R88") (pin "2") (pinfunction "2_2") (pintype "passive"))
      (node (ref "R89") (pin "1") (pinfunction "1_1") (pintype "passive"))
    )
    (net (code "25") (name "Net-(R84-Pad1)") (class "Default")
      (node (ref "R84") (pin "1") (pinfunction "1_1") (pintype "passive"))
      (node (ref "R86") (pin "1") (pinfunction "1_1") (pintype "passive"))
      (node (ref "R87") (pin "2") (pinfunction "2_2") (pintype "passive"))
    )
    (net (code "26") (name "Net-(TP13-TP)") (class "Default")
      (node (ref "C41") (pin "2") (pinfunction "2_2") (pintype "passive"))
      (node (ref "R72") (pin "2") (pinfunction "2_2") (pintype "passive"))
      (node (ref "TP13") (pin "1") (pinfunction "TP_1") (pintype "input"))
      (node (ref "U10") (pin "3") (pinfunction "CP2_3") (pintype "bidirectional"))
      (node (ref "U10") (pin "4") (pinfunction "IN+_4") (pintype "bidirectional"))
    )
    (net (code "27") (name "Net-(TP28-TP)") (class "Default")
      (node (ref "C32") (pin "2") (pinfunction "2_2") (pintype "passive"))
      (node (ref "R80") (pin "2") (pinfunction "2_2") (pintype "passive"))
      (node (ref "TP28") (pin "1") (pinfunction "TP_1") (pintype "input"))
      (node (ref "U13") (pin "3") (pinfunction "CP2_3") (pintype "bidirectional"))
      (node (ref "U13") (pin "4") (pinfunction "IN+_4") (pintype "bidirectional"))
    )
    (net (code "28") (name "Net-(TP57-TP)") (class "Default")
      (node (ref "C62") (pin "2") (pinfunction "2_2") (pintype "passive"))
      (node (ref "R119") (pin "2") (pinfunction "2_2") (pintype "passive"))
      (node (ref "TP57") (pin "1") (pinfunction "TP_1") (pintype "input"))
      (node (ref "U17") (pin "3") (pinfunction "CP2_3") (pintype "bidirectional"))
      (node (ref "U17") (pin "4") (pinfunction "IN+_4") (pintype "bidirectional"))
    )
    (net (code "29") (name "Net-(U6-CMTMOD)") (class "Default")
      (node (ref "R68") (pin "1") (pinfunction "1_1") (pintype "passive"))
      (node (ref "U6") (pin "20") (pinfunction "CMTMOD_20") (pintype "bidirectional"))
    )
    (net (code "30") (name "Net-(U6-CPN)") (class "Default")
      (node (ref "C11") (pin "2") (pinfunction "2_2") (pintype "passive"))
      (node (ref "U6") (pin "10") (pinfunction "CPN_10") (pintype "bidirectional"))
    )
    (net (code "31") (name "Net-(U6-CPP)") (class "Default")
      (node (ref "C11") (pin "1") (pinfunction "1_1") (pintype "passive"))
      (node (ref "U6") (pin "9") (pinfunction "CPP_9") (pintype "bidirectional"))
    )
    (net (code "32") (name "Net-(U6-DAA)") (class "Default")
      (node (ref "R67") (pin "2") (pinfunction "2_2") (pintype "passive"))
      (node (ref "U6") (pin "1") (pinfunction "DAA_1") (pintype "bidirectional"))
    )
    (net (code "33") (name "Net-(U6-RETRY)") (class "Default")
      (node (ref "C19") (pin "1") (pinfunction "1_1") (pintype "passive"))
      (node (ref "U6") (pin "22") (pinfunction "RETRY_22") (pintype "bidirectional"))
    )
    (net (code "34") (name "Net-(U6-VCP)") (class "Default")
      (node (ref "C12") (pin "2") (pinfunction "2_2") (pintype "passive"))
      (node (ref "U6") (pin "8") (pinfunction "VCP_8") (pintype "bidirectional"))
    )
    (net (code "35") (name "Net-(U6-VINT)") (class "Default")
      (node (ref "C28") (pin "1") (pinfunction "1_1") (pintype "passive"))
      (node (ref "U6") (pin "16") (pinfunction "VINT_16") (pintype "bidirectional"))
    )
    (net (code "36") (name "Net-(U7-CMTMOD)") (class "Default")
      (node (ref "R35") (pin "1") (pinfunction "1_1") (pintype "passive"))
      (node (ref "U7") (pin "20") (pinfunction "CMTMOD_20") (pintype "bidirectional"))
    )
    (net (code "37") (name "Net-(U7-CPN)") (class "Default")
      (node (ref "C13") (pin "2") (pinfunction "2_2") (pintype "passive"))
      (node (ref "U7") (pin "10") (pinfunction "CPN_10") (pintype "bidirectional"))
    )
    (net (code "38") (name "Net-(U7-CPP)") (class "Default")
      (node (ref "C13") (pin "1") (pinfunction "1_1") (pintype "passive"))
      (node (ref "U7") (pin "9") (pinfunction "CPP_9") (pintype "bidirectional"))
    )
    (net (code "39") (name "Net-(U7-DAA)") (class "Default")
      (node (ref "R21") (pin "2") (pinfunction "2_2") (pintype "passive"))
      (node (ref "U7") (pin "1") (pinfunction "DAA_1") (pintype "bidirectional"))
    )
    (net (code "40") (name "Net-(U7-RETRY)") (class "Default")
      (node (ref "C15") (pin "1") (pinfunction "1_1") (pintype "passive"))
      (node (ref "U7") (pin "22") (pinfunction "RETRY_22") (pintype "bidirectional"))
    )
    (net (code "41") (name "Net-(U7-VCP)") (class "Default")
      (node (ref "C14") (pin "2") (pinfunction "2_2") (pintype "passive"))
      (node (ref "U7") (pin "8") (pinfunction "VCP_8") (pintype "bidirectional"))
    )
    (net (code "42") (name "Net-(U7-VINT)") (class "Default")
      (node (ref "C35") (pin "1") (pinfunction "1_1") (pintype "passive"))
      (node (ref "U7") (pin "16") (pinfunction "VINT_16") (pintype "bidirectional"))
    )
    (net (code "43") (name "Net-(U8-IN+)") (class "Default")
      (node (ref "R15") (pin "2") (pinfunction "2_2") (pintype "passive"))
      (node (ref "R6") (pin "1") (pinfunction "1_1") (pintype "passive"))
      (node (ref "U8") (pin "3") (pinfunction "IN+_3") (pintype "input"))
    )
    (net (code "44") (name "Net-(U8-IN-)") (class "Default")
      (node (ref "R12") (pin "1") (pinfunction "1_1") (pintype "passive"))
      (node (ref "R16") (pin "1") (pinfunction "1_1") (pintype "passive"))
      (node (ref "U8") (pin "4") (pinfunction "IN-_4") (pintype "input"))
    )
    (net (code "45") (name "Net-(U9-BUSY)") (class "Default")
      (node (ref "R23") (pin "2") (pinfunction "2_2") (pintype "passive"))
      (node (ref "U9") (pin "13") (pinfunction "BUSY_13") (pintype "output"))
    )
    (net (code "46") (name "Net-(U9-CH3)") (class "Default")
      (node (ref "R14") (pin "1") (pinfunction "1_1") (pintype "passive"))
      (node (ref "U9") (pin "5") (pinfunction "CH3_5") (pintype "input"))
    )
    (net (code "47") (name "Net-(U9-~{SHDN})") (class "Default")
      (node (ref "C69") (pin "1") (pinfunction "1_1") (pintype "passive"))
      (node (ref "R5") (pin "1") (pinfunction "1_1") (pintype "passive"))
      (node (ref "U9") (pin "7") (pinfunction "~{SHDN}_7") (pintype "passive"))
    )
    (net (code "48") (name "Net-(U10-CP1)") (class "Default")
      (node (ref "C38") (pin "2") (pinfunction "2_2") (pintype "passive"))
      (node (ref "U10") (pin "2") (pinfunction "CP1_2") (pintype "bidirectional"))
    )
    (net (code "49") (name "Net-(U10-TACH-)") (class "Default")
      (node (ref "R48") (pin "1") (pinfunction "1_1") (pintype "passive"))
      (node (ref "R49") (pin "2") (pinfunction "2_2") (pintype "passive"))
      (node (ref "U10") (pin "11") (pinfunction "TACH-_11") (pintype "bidirectional"))
    )
    (net (code "50") (name "Net-(U12-IN+)") (class "Default")
      (node (ref "R25") (pin "1") (pinfunction "1_1") (pintype "passive"))
      (node (ref "R32") (pin "2") (pinfunction "2_2") (pintype "passive"))
      (node (ref "U12") (pin "3") (pinfunction "IN+_3") (pintype "input"))
    )
    (net (code "51") (name "Net-(U12-IN-)") (class "Default")
      (node (ref "R31") (pin "1") (pinfunction "1_1") (pintype "passive"))
      (node (ref "R33") (pin "1") (pinfunction "1_1") (pintype "passive"))
      (node (ref "U12") (pin "4") (pinfunction "IN-_4") (pintype "input"))
    )
    (net (code "52") (name "Net-(U13-CP1)") (class "Default")
      (node (ref "C31") (pin "2") (pinfunction "2_2") (pintype "passive"))
      (node (ref "U13") (pin "2") (pinfunction "CP1_2") (pintype "bidirectional"))
    )
    (net (code "53") (name "Net-(U13-TACH-)") (class "Default")
      (node (ref "R78") (pin "1") (pinfunction "1_1") (pintype "passive"))
      (node (ref "R79") (pin "2") (pinfunction "2_2") (pintype "passive"))
      (node (ref "U13") (pin "11") (pinfunction "TACH-_11") (pintype "bidirectional"))
    )
    (net (code "54") (name "Net-(U14-BUSY)") (class "Default")
      (node (ref "R37") (pin "2") (pinfunction "2_2") (pintype "passive"))
      (node (ref "U14") (pin "13") (pinfunction "BUSY_13") (pintype "output"))
    )
    (net (code "55") (name "Net-(U14-CH3)") (class "Default")
      (node (ref "R13") (pin "1") (pinfunction "1_1") (pintype "passive"))
      (node (ref "U14") (pin "5") (pinfunction "CH3_5") (pintype "input"))
    )
    (net (code "56") (name "Net-(U14-~{SHDN})") (class "Default")
      (node (ref "C76") (pin "1") (pinfunction "1_1") (pintype "passive"))
      (node (ref "R29") (pin "1") (pinfunction "1_1") (pintype "passive"))
      (node (ref "U14") (pin "7") (pinfunction "~{SHDN}_7") (pintype "passive"))
    )
    (net (code "57") (name "Net-(U16-CMTMOD)") (class "Default")
      (node (ref "R111") (pin "1") (pinfunction "1_1") (pintype "passive"))
      (node (ref "U16") (pin "20") (pinfunction "CMTMOD_20") (pintype "bidirectional"))
    )
    (net (code "58") (name "Net-(U16-CPN)") (class "Default")
      (node (ref "C54") (pin "2") (pinfunction "2_2") (pintype "passive"))
      (node (ref "U16") (pin "10") (pinfunction "CPN_10") (pintype "bidirectional"))
    )
    (net (code "59") (name "Net-(U16-CPP)") (class "Default")
      (node (ref "C54") (pin "1") (pinfunction "1_1") (pintype "passive"))
      (node (ref "U16") (pin "9") (pinfunction "CPP_9") (pintype "bidirectional"))
    )
    (net (code "60") (name "Net-(U16-DAA)") (class "Default")
      (node (ref "R110") (pin "2") (pinfunction "2_2") (pintype "passive"))
      (node (ref "U16") (pin "1") (pinfunction "DAA_1") (pintype "bidirectional"))
    )
    (net (code "61") (name "Net-(U16-RETRY)") (class "Default")
      (node (ref "C57") (pin "1") (pinfunction "1_1") (pintype "passive"))
      (node (ref "U16") (pin "22") (pinfunction "RETRY_22") (pintype "bidirectional"))
    )
    (net (code "62") (name "Net-(U16-VCP)") (class "Default")
      (node (ref "C55") (pin "2") (pinfunction "2_2") (pintype "passive"))
      (node (ref "U16") (pin "8") (pinfunction "VCP_8") (pintype "bidirectional"))
    )
    (net (code "63") (name "Net-(U16-VINT)") (class "Default")
      (node (ref "C59") (pin "1") (pinfunction "1_1") (pintype "passive"))
      (node (ref "U16") (pin "16") (pinfunction "VINT_16") (pintype "bidirectional"))
    )
    (net (code "64") (name "Net-(U17-CP1)") (class "Default")
      (node (ref "C61") (pin "2") (pinfunction "2_2") (pintype "passive"))
      (node (ref "U17") (pin "2") (pinfunction "CP1_2") (pintype "bidirectional"))
    )
    (net (code "65") (name "Net-(U17-TACH-)") (class "Default")
      (node (ref "R117") (pin "1") (pinfunction "1_1") (pintype "passive"))
      (node (ref "R118") (pin "2") (pinfunction "2_2") (pintype "passive"))
      (node (ref "U17") (pin "11") (pinfunction "TACH-_11") (pintype "bidirectional"))
    )
    (net (code "66") (name "Net-(U19-IN+)") (class "Default")
      (node (ref "R81") (pin "1") (pinfunction "1_1") (pintype "passive"))
      (node (ref "R84") (pin "2") (pinfunction "2_2") (pintype "passive"))
      (node (ref "U19") (pin "3") (pinfunction "IN+_3") (pintype "input"))
    )
    (net (code "67") (name "Net-(U19-IN-)") (class "Default")
      (node (ref "R83") (pin "1") (pinfunction "1_1") (pintype "passive"))
      (node (ref "R85") (pin "1") (pinfunction "1_1") (pintype "passive"))
      (node (ref "U19") (pin "4") (pinfunction "IN-_4") (pintype "input"))
    )
    (net (code "68") (name "Net-(U20-BUSY)") (class "Default")
      (node (ref "R51") (pin "2") (pinfunction "2_2") (pintype "passive"))
      (node (ref "U20") (pin "13") (pinfunction "BUSY_13") (pintype "output"))
    )
    (net (code "69") (name "Net-(U20-CH3)") (class "Default")
      (node (ref "R4") (pin "1") (pinfunction "1_1") (pintype "passive"))
      (node (ref "U20") (pin "5") (pinfunction "CH3_5") (pintype "input"))
    )
    (net (code "70") (name "Net-(U20-~{SHDN})") (class "Default")
      (node (ref "C90") (pin "1") (pinfunction "1_1") (pintype "passive"))
      (node (ref "R50") (pin "1") (pinfunction "1_1") (pintype "passive"))
      (node (ref "U20") (pin "7") (pinfunction "~{SHDN}_7") (pintype "passive"))
    )
    (net (code "71") (name "OUT1_X") (class "Default")
      (node (ref "JP2") (pin "1") (pinfunction "1_1") (pintype "passive"))
      (node (ref "R11") (pin "1") (pinfunction "1_1") (pintype "passive"))
      (node (ref "R12") (pin "2") (pinfunction "2_2") (pintype "passive"))
      (node (ref "R22") (pin "1") (pinfunction "1_1") (pintype "passive"))
      (node (ref "TP21") (pin "1") (pinfunction "TP_1") (pintype "input"))
    )
    (net (code "72") (name "OUT1_Y") (class "Default")
      (node (ref "JP3") (pin "1") (pinfunction "1_1") (pintype "passive"))
      (node (ref "R30") (pin "1") (pinfunction "1_1") (pintype "passive"))
      (node (ref "R31") (pin "2") (pinfunction "2_2") (pintype "passive"))
      (node (ref "R42") (pin "1") (pinfunction "1_1") (pintype "passive"))
      (node (ref "TP39") (pin "1") (pinfunction "TP_1") (pintype "input"))
    )
    (net (code "73") (name "OUT1_Z") (class "Default")
      (node (ref "JP5") (pin "1") (pinfunction "1_1") (pintype "passive"))
      (node (ref "R82") (pin "1") (pinfunction "1_1") (pintype "passive"))
      (node (ref "R83") (pin "2") (pinfunction "2_2") (pintype "passive"))
      (node (ref "R88") (pin "1") (pinfunction "1_1") (pintype "passive"))
      (node (ref "TP62") (pin "1") (pinfunction "TP_1") (pintype "input"))
    )
    (net (code "74") (name "OUT2_X") (class "Default")
      (node (ref "JP2") (pin "2") (pinfunction "2_2") (pintype "passive"))
      (node (ref "TP22") (pin "1") (pinfunction "TP_1") (pintype "input"))
      (node (ref "U1") (pin "5") (pinfunction "OUTB_5") (pintype "bidirectional"))
    )
    (net (code "75") (name "OUT2_Y") (class "Default")
      (node (ref "JP3") (pin "2") (pinfunction "2_2") (pintype "passive"))
      (node (ref "TP40") (pin "1") (pinfunction "TP_1") (pintype "input"))
      (node (ref "U2") (pin "5") (pinfunction "OUTB_5") (pintype "bidirectional"))
    )
    (net (code "76") (name "OUT2_Z") (class "Default")
      (node (ref "JP5") (pin "2") (pinfunction "2_2") (pintype "passive"))
      (node (ref "TP63") (pin "1") (pinfunction "TP_1") (pintype "input"))
      (node (ref "U3") (pin "5") (pinfunction "OUTB_5") (pintype "bidirectional"))
    )
    (net (code "77") (name "RW_X_DIR") (class "Default")
      (node (ref "JP1B") (pin "3") (pinfunction "3_3") (pintype "passive"))
      (node (ref "U7") (pin "23") (pinfunction "FR_23") (pintype "bidirectional"))
    )
    (net (code "78") (name "RW_X_I_SENS") (class "Default")
      (node (ref "R7") (pin "2") (pinfunction "2_2") (pintype "passive"))
      (node (ref "TP11") (pin "1") (pinfunction "TP_1") (pintype "input"))
      (node (ref "U14") (pin "3") (pinfunction "CH1_3") (pintype "input"))
      (node (ref "U7") (pin "17") (pinfunction "CS_17") (pintype "bidirectional"))
    )
    (net (code "79") (name "RW_X_LOCK") (class "Default")
      (node (ref "JP1A") (pin "11") (pinfunction "11_11") (pintype "passive"))
      (node (ref "R9") (pin "2") (pinfunction "2_2") (pintype "passive"))
      (node (ref "U7") (pin "18") (pinfunction "RD_18") (pintype "bidirectional"))
    )
    (net (code "80") (name "RW_X_OUTFG") (class "Default")
      (node (ref "R8") (pin "2") (pinfunction "2_2") (pintype "passive"))
      (node (ref "TP23") (pin "1") (pinfunction "TP_1") (pintype "input"))
      (node (ref "U10") (pin "1") (pinfunction "TACH+_1") (pintype "bidirectional"))
      (node (ref "U7") (pin "24") (pinfunction "FG_24") (pintype "bidirectional"))
    )
    (net (code "81") (name "RW_X_SPD") (class "Default")
      (node (ref "R44") (pin "2") (pinfunction "2_2") (pintype "passive"))
      (node (ref "TP12") (pin "1") (pinfunction "TP_1") (pintype "input"))
      (node (ref "U10") (pin "10") (pinfunction "IN-_10") (pintype "bidirectional"))
      (node (ref "U10") (pin "5") (pinfunction "EMIT_5") (pintype "bidirectional"))
      (node (ref "U20") (pin "3") (pinfunction "CH1_3") (pintype "input"))
    )
    (net (code "82") (name "RW_X_SPEED_CTRL") (class "Default")
      (node (ref "JP1A") (pin "9") (pinfunction "9_9") (pintype "passive"))
      (node (ref "U7") (pin "19") (pinfunction "PWM_19") (pintype "bidirectional"))
    )
    (net (code "83") (name "RW_Y_DIR") (class "Default")
      (node (ref "JP1B") (pin "5") (pinfunction "5_5") (pintype "passive"))
      (node (ref "U16") (pin "23") (pinfunction "FR_23") (pintype "bidirectional"))
    )
    (net (code "84") (name "RW_Y_I_SENS") (class "Default")
      (node (ref "R104") (pin "2") (pinfunction "2_2") (pintype "passive"))
      (node (ref "TP55") (pin "1") (pinfunction "TP_1") (pintype "input"))
      (node (ref "U14") (pin "4") (pinfunction "CH2_4") (pintype "input"))
      (node (ref "U16") (pin "17") (pinfunction "CS_17") (pintype "bidirectional"))
    )
    (net (code "85") (name "RW_Y_LOCK") (class "Default")
      (node (ref "JP1B") (pin "9") (pinfunction "9_9") (pintype "passive"))
      (node (ref "R106") (pin "2") (pinfunction "2_2") (pintype "passive"))
      (node (ref "U16") (pin "18") (pinfunction "RD_18") (pintype "bidirectional"))
    )
    (net (code "86") (name "RW_Y_OUTFG") (class "Default")
      (node (ref "R105") (pin "2") (pinfunction "2_2") (pintype "passive"))
      (node (ref "TP61") (pin "1") (pinfunction "TP_1") (pintype "input"))
      (node (ref "U16") (pin "24") (pinfunction "FG_24") (pintype "bidirectional"))
      (node (ref "U17") (pin "1") (pinfunction "TACH+_1") (pintype "bidirectional"))
    )
    (net (code "87") (name "RW_Y_SPD") (class "Default")
      (node (ref "R116") (pin "2") (pinfunction "2_2") (pintype "passive"))
      (node (ref "TP56") (pin "1") (pinfunction "TP_1") (pintype "input"))
      (node (ref "U17") (pin "10") (pinfunction "IN-_10") (pintype "bidirectional"))
      (node (ref "U17") (pin "5") (pinfunction "EMIT_5") (pintype "bidirectional"))
      (node (ref "U20") (pin "4") (pinfunction "CH2_4") (pintype "input"))
    )
    (net (code "88") (name "RW_Y_SPEED_CTRL") (class "Default")
      (node (ref "JP1B") (pin "7") (pinfunction "7_7") (pintype "passive"))
      (node (ref "U16") (pin "19") (pinfunction "PWM_19") (pintype "bidirectional"))
    )
    (net (code "89") (name "RW_Z_DIR") (class "Default")
      (node (ref "JP1A") (pin "3") (pinfunction "3_3") (pintype "passive"))
      (node (ref "U6") (pin "23") (pinfunction "FR_23") (pintype "bidirectional"))
    )
    (net (code "90") (name "RW_Z_I_SENS") (class "Default")
      (node (ref "R61") (pin "2") (pinfunction "2_2") (pintype "passive"))
      (node (ref "TP26") (pin "1") (pinfunction "TP_1") (pintype "input"))
      (node (ref "U14") (pin "2") (pinfunction "CH0_2") (pintype "input"))
      (node (ref "U6") (pin "17") (pinfunction "CS_17") (pintype "bidirectional"))
    )
    (net (code "91") (name "RW_Z_LOCK") (class "Default")
      (node (ref "JP1A") (pin "7") (pinfunction "7_7") (pintype "passive"))
      (node (ref "R63") (pin "2") (pinfunction "2_2") (pintype "passive"))
      (node (ref "U6") (pin "18") (pinfunction "RD_18") (pintype "bidirectional"))
    )
    (net (code "92") (name "RW_Z_OUTFG") (class "Default")
      (node (ref "R62") (pin "2") (pinfunction "2_2") (pintype "passive"))
      (node (ref "TP38") (pin "1") (pinfunction "TP_1") (pintype "input"))
      (node (ref "U13") (pin "1") (pinfunction "TACH+_1") (pintype "bidirectional"))
      (node (ref "U6") (pin "24") (pinfunction "FG_24") (pintype "bidirectional"))
    )
    (net (code "93") (name "RW_Z_SPD") (class "Default")
      (node (ref "R77") (pin "2") (pinfunction "2_2") (pintype "passive"))
      (node (ref "TP27") (pin "1") (pinfunction "TP_1") (pintype "input"))
      (node (ref "U13") (pin "10") (pinfunction "IN-_10") (pintype "bidirectional"))
      (node (ref "U13") (pin "5") (pinfunction "EMIT_5") (pintype "bidirectional"))
      (node (ref "U20") (pin "2") (pinfunction "CH0_2") (pintype "input"))
    )
    (net (code "94") (name "RW_Z_SPEED_CTRL") (class "Default")
      (node (ref "JP1A") (pin "5") (pinfunction "5_5") (pintype "passive"))
      (node (ref "U6") (pin "19") (pinfunction "PWM_19") (pintype "bidirectional"))
    )
    (net (code "95") (name "UCB0_SPI_CLK") (class "Default")
      (node (ref "JP1B") (pin "6") (pinfunction "6_6") (pintype "passive"))
      (node (ref "U14") (pin "16") (pinfunction "DCLK_16") (pintype "input"))
      (node (ref "U20") (pin "16") (pinfunction "DCLK_16") (pintype "input"))
      (node (ref "U9") (pin "16") (pinfunction "DCLK_16") (pintype "input"))
    )
    (net (code "96") (name "UCB0_SPI_MISO") (class "Default")
      (node (ref "JP1B") (pin "10") (pinfunction "10_10") (pintype "passive"))
      (node (ref "U14") (pin "12") (pinfunction "DOUT_12") (pintype "output"))
      (node (ref "U20") (pin "12") (pinfunction "DOUT_12") (pintype "output"))
      (node (ref "U9") (pin "12") (pinfunction "DOUT_12") (pintype "output"))
    )
    (net (code "97") (name "UCB0_SPI_MOSI") (class "Default")
      (node (ref "JP1B") (pin "8") (pinfunction "8_8") (pintype "passive"))
      (node (ref "U14") (pin "14") (pinfunction "DIN_14") (pintype "input"))
      (node (ref "U20") (pin "14") (pinfunction "DIN_14") (pintype "input"))
      (node (ref "U9") (pin "14") (pinfunction "DIN_14") (pintype "input"))
    )
    (net (code "98") (name "VINT{slash}2_X") (class "Default")
      (node (ref "C16") (pin "1") (pinfunction "1_1") (pintype "passive"))
      (node (ref "R1") (pin "1") (pinfunction "1_1") (pintype "passive"))
      (node (ref "R2") (pin "2") (pinfunction "2_2") (pintype "passive"))
      (node (ref "U7") (pin "3") (pinfunction "U_HN_3") (pintype "bidirectional"))
      (node (ref "U7") (pin "5") (pinfunction "V_HN_5") (pintype "bidirectional"))
      (node (ref "U7") (pin "7") (pinfunction "W_HN_7") (pintype "bidirectional"))
    )
    (net (code "99") (name "VINT{slash}2_Y") (class "Default")
      (node (ref "C58") (pin "1") (pinfunction "1_1") (pintype "passive"))
      (node (ref "R102") (pin "1") (pinfunction "1_1") (pintype "passive"))
      (node (ref "R103") (pin "2") (pinfunction "2_2") (pintype "passive"))
      (node (ref "U16") (pin "3") (pinfunction "U_HN_3") (pintype "bidirectional"))
      (node (ref "U16") (pin "5") (pinfunction "V_HN_5") (pintype "bidirectional"))
      (node (ref "U16") (pin "7") (pinfunction "W_HN_7") (pintype "bidirectional"))
    )
    (net (code "100") (name "VINT{slash}2_Z") (class "Default")
      (node (ref "C20") (pin "1") (pinfunction "1_1") (pintype "passive"))
      (node (ref "R59") (pin "1") (pinfunction "1_1") (pintype "passive"))
      (node (ref "R60") (pin "2") (pinfunction "2_2") (pintype "passive"))
      (node (ref "U6") (pin "3") (pinfunction "U_HN_3") (pintype "bidirectional"))
      (node (ref "U6") (pin "5") (pinfunction "V_HN_5") (pintype "bidirectional"))
      (node (ref "U6") (pin "7") (pinfunction "W_HN_7") (pintype "bidirectional"))
    )
    (net (code "101") (name "X_DNC_1") (class "Default")
      (node (ref "R36") (pin "1") (pinfunction "1_1") (pintype "passive"))
      (node (ref "U10") (pin "6") (pinfunction "DNC_1_6") (pintype "bidirectional"))
    )
    (net (code "102") (name "X_DNC_2") (class "Default")
      (node (ref "R39") (pin "1") (pinfunction "1_1") (pintype "passive"))
      (node (ref "U10") (pin "7") (pinfunction "DNC_2_7") (pintype "bidirectional"))
    )
    (net (code "103") (name "X_DNC_3") (class "Default")
      (node (ref "R43") (pin "1") (pinfunction "1_1") (pintype "passive"))
      (node (ref "U10") (pin "14") (pinfunction "DNC_3_14") (pintype "bidirectional"))
    )
    (net (code "104") (name "X_DNC_4") (class "Default")
      (node (ref "R40") (pin "1") (pinfunction "1_1") (pintype "passive"))
      (node (ref "U10") (pin "13") (pinfunction "DNC_4_13") (pintype "bidirectional"))
    )
    (net (code "105") (name "X_HALL_A") (class "Default")
      (node (ref "J4") (pin "3") (pinfunction "3_3") (pintype "bidirectional"))
      (node (ref "R19") (pin "1") (pinfunction "1_1") (pintype "passive"))
      (node (ref "TP5") (pin "1") (pinfunction "TP_1") (pintype "input"))
      (node (ref "U7") (pin "2") (pinfunction "U_HP_2") (pintype "bidirectional"))
    )
    (net (code "106") (name "X_HALL_B") (class "Default")
      (node (ref "J4") (pin "4") (pinfunction "4_4") (pintype "bidirectional"))
      (node (ref "R10") (pin "1") (pinfunction "1_1") (pintype "passive"))
      (node (ref "TP4") (pin "1") (pinfunction "TP_1") (pintype "input"))
      (node (ref "U7") (pin "4") (pinfunction "V_HP_4") (pintype "bidirectional"))
    )
    (net (code "107") (name "X_HALL_C") (class "Default")
      (node (ref "J4") (pin "2") (pinfunction "2_2") (pintype "bidirectional"))
      (node (ref "R20") (pin "1") (pinfunction "1_1") (pintype "passive"))
      (node (ref "TP2") (pin "1") (pinfunction "TP_1") (pintype "input"))
      (node (ref "U7") (pin "6") (pinfunction "W_HP_6") (pintype "bidirectional"))
    )
    (net (code "108") (name "X_PHASE_A") (class "Default")
      (node (ref "J4") (pin "10") (pinfunction "10_10") (pintype "bidirectional"))
      (node (ref "J4") (pin "11") (pinfunction "11_11") (pintype "bidirectional"))
      (node (ref "TP14") (pin "1") (pinfunction "TP_1") (pintype "input"))
      (node (ref "U7") (pin "14") (pinfunction "U_14") (pintype "bidirectional"))
    )
    (net (code "109") (name "X_PHASE_B") (class "Default")
      (node (ref "J4") (pin "8") (pinfunction "8_8") (pintype "bidirectional"))
      (node (ref "J4") (pin "9") (pinfunction "9_9") (pintype "bidirectional"))
      (node (ref "TP15") (pin "1") (pinfunction "TP_1") (pintype "input"))
      (node (ref "U7") (pin "13") (pinfunction "V_13") (pintype "bidirectional"))
    )
    (net (code "110") (name "X_PHASE_C") (class "Default")
      (node (ref "J4") (pin "6") (pinfunction "6_6") (pintype "bidirectional"))
      (node (ref "J4") (pin "7") (pinfunction "7_7") (pintype "bidirectional"))
      (node (ref "TP16") (pin "1") (pinfunction "TP_1") (pintype "input"))
      (node (ref "U7") (pin "11") (pinfunction "W_11") (pintype "bidirectional"))
    )
    (net (code "111") (name "Y_DNC_1") (class "Default")
      (node (ref "R112") (pin "1") (pinfunction "1_1") (pintype "passive"))
      (node (ref "U17") (pin "6") (pinfunction "DNC_1_6") (pintype "bidirectional"))
    )
    (net (code "112") (name "Y_DNC_2") (class "Default")
      (node (ref "R113") (pin "1") (pinfunction "1_1") (pintype "passive"))
      (node (ref "U17") (pin "7") (pinfunction "DNC_2_7") (pintype "bidirectional"))
    )
    (net (code "113") (name "Y_DNC_3") (class "Default")
      (node (ref "R115") (pin "1") (pinfunction "1_1") (pintype "passive"))
      (node (ref "U17") (pin "14") (pinfunction "DNC_3_14") (pintype "bidirectional"))
    )
    (net (code "114") (name "Y_DNC_4") (class "Default")
      (node (ref "R114") (pin "1") (pinfunction "1_1") (pintype "passive"))
      (node (ref "U17") (pin "13") (pinfunction "DNC_4_13") (pintype "bidirectional"))
    )
    (net (code "115") (name "Y_HALL_A") (class "Default")
      (node (ref "J11") (pin "3") (pinfunction "3_3") (pintype "bidirectional"))
      (node (ref "R108") (pin "1") (pinfunction "1_1") (pintype "passive"))
      (node (ref "TP53") (pin "1") (pinfunction "TP_1") (pintype "input"))
      (node (ref "U16") (pin "2") (pinfunction "U_HP_2") (pintype "bidirectional"))
    )
    (net (code "116") (name "Y_HALL_B") (class "Default")
      (node (ref "J11") (pin "4") (pinfunction "4_4") (pintype "bidirectional"))
      (node (ref "R107") (pin "1") (pinfunction "1_1") (pintype "passive"))
      (node (ref "TP50") (pin "1") (pinfunction "TP_1") (pintype "input"))
      (node (ref "U16") (pin "4") (pinfunction "V_HP_4") (pintype "bidirectional"))
    )
    (net (code "117") (name "Y_HALL_C") (class "Default")
      (node (ref "J11") (pin "2") (pinfunction "2_2") (pintype "bidirectional"))
      (node (ref "R109") (pin "1") (pinfunction "1_1") (pintype "passive"))
      (node (ref "TP49") (pin "1") (pinfunction "TP_1") (pintype "input"))
      (node (ref "U16") (pin "6") (pinfunction "W_HP_6") (pintype "bidirectional"))
    )
    (net (code "118") (name "Y_PHASE_A") (class "Default")
      (node (ref "J11") (pin "10") (pinfunction "10_10") (pintype "bidirectional"))
      (node (ref "J11") (pin "11") (pinfunction "11_11") (pintype "bidirectional"))
      (node (ref "TP58") (pin "1") (pinfunction "TP_1") (pintype "input"))
      (node (ref "U16") (pin "14") (pinfunction "U_14") (pintype "bidirectional"))
    )
    (net (code "119") (name "Y_PHASE_B") (class "Default")
      (node (ref "J11") (pin "8") (pinfunction "8_8") (pintype "bidirectional"))
      (node (ref "J11") (pin "9") (pinfunction "9_9") (pintype "bidirectional"))
      (node (ref "TP59") (pin "1") (pinfunction "TP_1") (pintype "input"))
      (node (ref "U16") (pin "13") (pinfunction "V_13") (pintype "bidirectional"))
    )
    (net (code "120") (name "Y_PHASE_C") (class "Default")
      (node (ref "J11") (pin "6") (pinfunction "6_6") (pintype "bidirectional"))
      (node (ref "J11") (pin "7") (pinfunction "7_7") (pintype "bidirectional"))
      (node (ref "TP60") (pin "1") (pinfunction "TP_1") (pintype "input"))
      (node (ref "U16") (pin "11") (pinfunction "W_11") (pintype "bidirectional"))
    )
    (net (code "121") (name "Z_DNC_1") (class "Default")
      (node (ref "R69") (pin "1") (pinfunction "1_1") (pintype "passive"))
      (node (ref "U13") (pin "6") (pinfunction "DNC_1_6") (pintype "bidirectional"))
    )
    (net (code "122") (name "Z_DNC_2") (class "Default")
      (node (ref "R70") (pin "1") (pinfunction "1_1") (pintype "passive"))
      (node (ref "U13") (pin "7") (pinfunction "DNC_2_7") (pintype "bidirectional"))
    )
    (net (code "123") (name "Z_DNC_3") (class "Default")
      (node (ref "R75") (pin "1") (pinfunction "1_1") (pintype "passive"))
      (node (ref "U13") (pin "14") (pinfunction "DNC_3_14") (pintype "bidirectional"))
    )
    (net (code "124") (name "Z_DNC_4") (class "Default")
      (node (ref "R71") (pin "1") (pinfunction "1_1") (pintype "passive"))
      (node (ref "U13") (pin "13") (pinfunction "DNC_4_13") (pintype "bidirectional"))
    )
    (net (code "125") (name "Z_HALL_A") (class "Default")
      (node (ref "J2") (pin "3") (pinfunction "3_3") (pintype "bidirectional"))
      (node (ref "R65") (pin "1") (pinfunction "1_1") (pintype "passive"))
      (node (ref "TP20") (pin "1") (pinfunction "TP_1") (pintype "input"))
      (node (ref "U6") (pin "2") (pinfunction "U_HP_2") (pintype "bidirectional"))
    )
    (net (code "126") (name "Z_HALL_B") (class "Default")
      (node (ref "J2") (pin "4") (pinfunction "4_4") (pintype "bidirectional"))
      (node (ref "R64") (pin "1") (pinfunction "1_1") (pintype "passive"))
      (node (ref "TP19") (pin "1") (pinfunction "TP_1") (pintype "input"))
      (node (ref "U6") (pin "4") (pinfunction "V_HP_4") (pintype "bidirectional"))
    )
    (net (code "127") (name "Z_HALL_C") (class "Default")
      (node (ref "J2") (pin "2") (pinfunction "2_2") (pintype "bidirectional"))
      (node (ref "R66") (pin "1") (pinfunction "1_1") (pintype "passive"))
      (node (ref "TP18") (pin "1") (pinfunction "TP_1") (pintype "input"))
      (node (ref "U6") (pin "6") (pinfunction "W_HP_6") (pintype "bidirectional"))
    )
    (net (code "128") (name "Z_PHASE_A") (class "Default")
      (node (ref "J2") (pin "10") (pinfunction "10_10") (pintype "bidirectional"))
      (node (ref "J2") (pin "11") (pinfunction "11_11") (pintype "bidirectional"))
      (node (ref "TP29") (pin "1") (pinfunction "TP_1") (pintype "input"))
      (node (ref "U6") (pin "14") (pinfunction "U_14") (pintype "bidirectional"))
    )
    (net (code "129") (name "Z_PHASE_B") (class "Default")
      (node (ref "J2") (pin "8") (pinfunction "8_8") (pintype "bidirectional"))
      (node (ref "J2") (pin "9") (pinfunction "9_9") (pintype "bidirectional"))
      (node (ref "TP33") (pin "1") (pinfunction "TP_1") (pintype "input"))
      (node (ref "U6") (pin "13") (pinfunction "V_13") (pintype "bidirectional"))
    )
    (net (code "130") (name "Z_PHASE_C") (class "Default")
      (node (ref "J2") (pin "6") (pinfunction "6_6") (pintype "bidirectional"))
      (node (ref "J2") (pin "7") (pinfunction "7_7") (pintype "bidirectional"))
      (node (ref "TP37") (pin "1") (pinfunction "TP_1") (pintype "input"))
      (node (ref "U6") (pin "11") (pinfunction "W_11") (pintype "bidirectional"))
    )
    (net (code "131") (name "unconnected-(MH5-MOUNT-Pad1)") (class "Default")
      (node (ref "MH5") (pin "1") (pinfunction "MOUNT_1") (pintype "no_connect"))
    )
    (net (code "132") (name "unconnected-(MH6-MOUNT-Pad1)") (class "Default")
      (node (ref "MH6") (pin "1") (pinfunction "MOUNT_1") (pintype "no_connect"))
    )
    (net (code "133") (name "unconnected-(MH7-MOUNT-Pad1)") (class "Default")
      (node (ref "MH7") (pin "1") (pinfunction "MOUNT_1") (pintype "no_connect"))
    )
    (net (code "134") (name "unconnected-(MH8-MOUNT-Pad1)") (class "Default")
      (node (ref "MH8") (pin "1") (pinfunction "MOUNT_1") (pintype "no_connect"))
    )
    (net (code "135") (name "~{CS}_CURR_SENSE_MTQR") (class "Default")
      (node (ref "JP1B") (pin "11") (pinfunction "11_11") (pintype "passive"))
      (node (ref "U9") (pin "15") (pinfunction "~{CS}_15") (pintype "input"))
    )
    (net (code "136") (name "~{CS}_CURR_SENSE_RW") (class "Default")
      (node (ref "JP1B") (pin "1") (pinfunction "1_1") (pintype "passive"))
      (node (ref "U14") (pin "15") (pinfunction "~{CS}_15") (pintype "input"))
    )
    (net (code "137") (name "~{CS}_SPD_SENSE_RW") (class "Default")
      (node (ref "JP1B") (pin "12") (pinfunction "12_12") (pintype "passive"))
      (node (ref "U20") (pin "15") (pinfunction "~{CS}_15") (pintype "input"))
    )
  )
)
